# Keybon12_REV_1_0.net
KiCad netlist of a schematic drawn in EAGLE
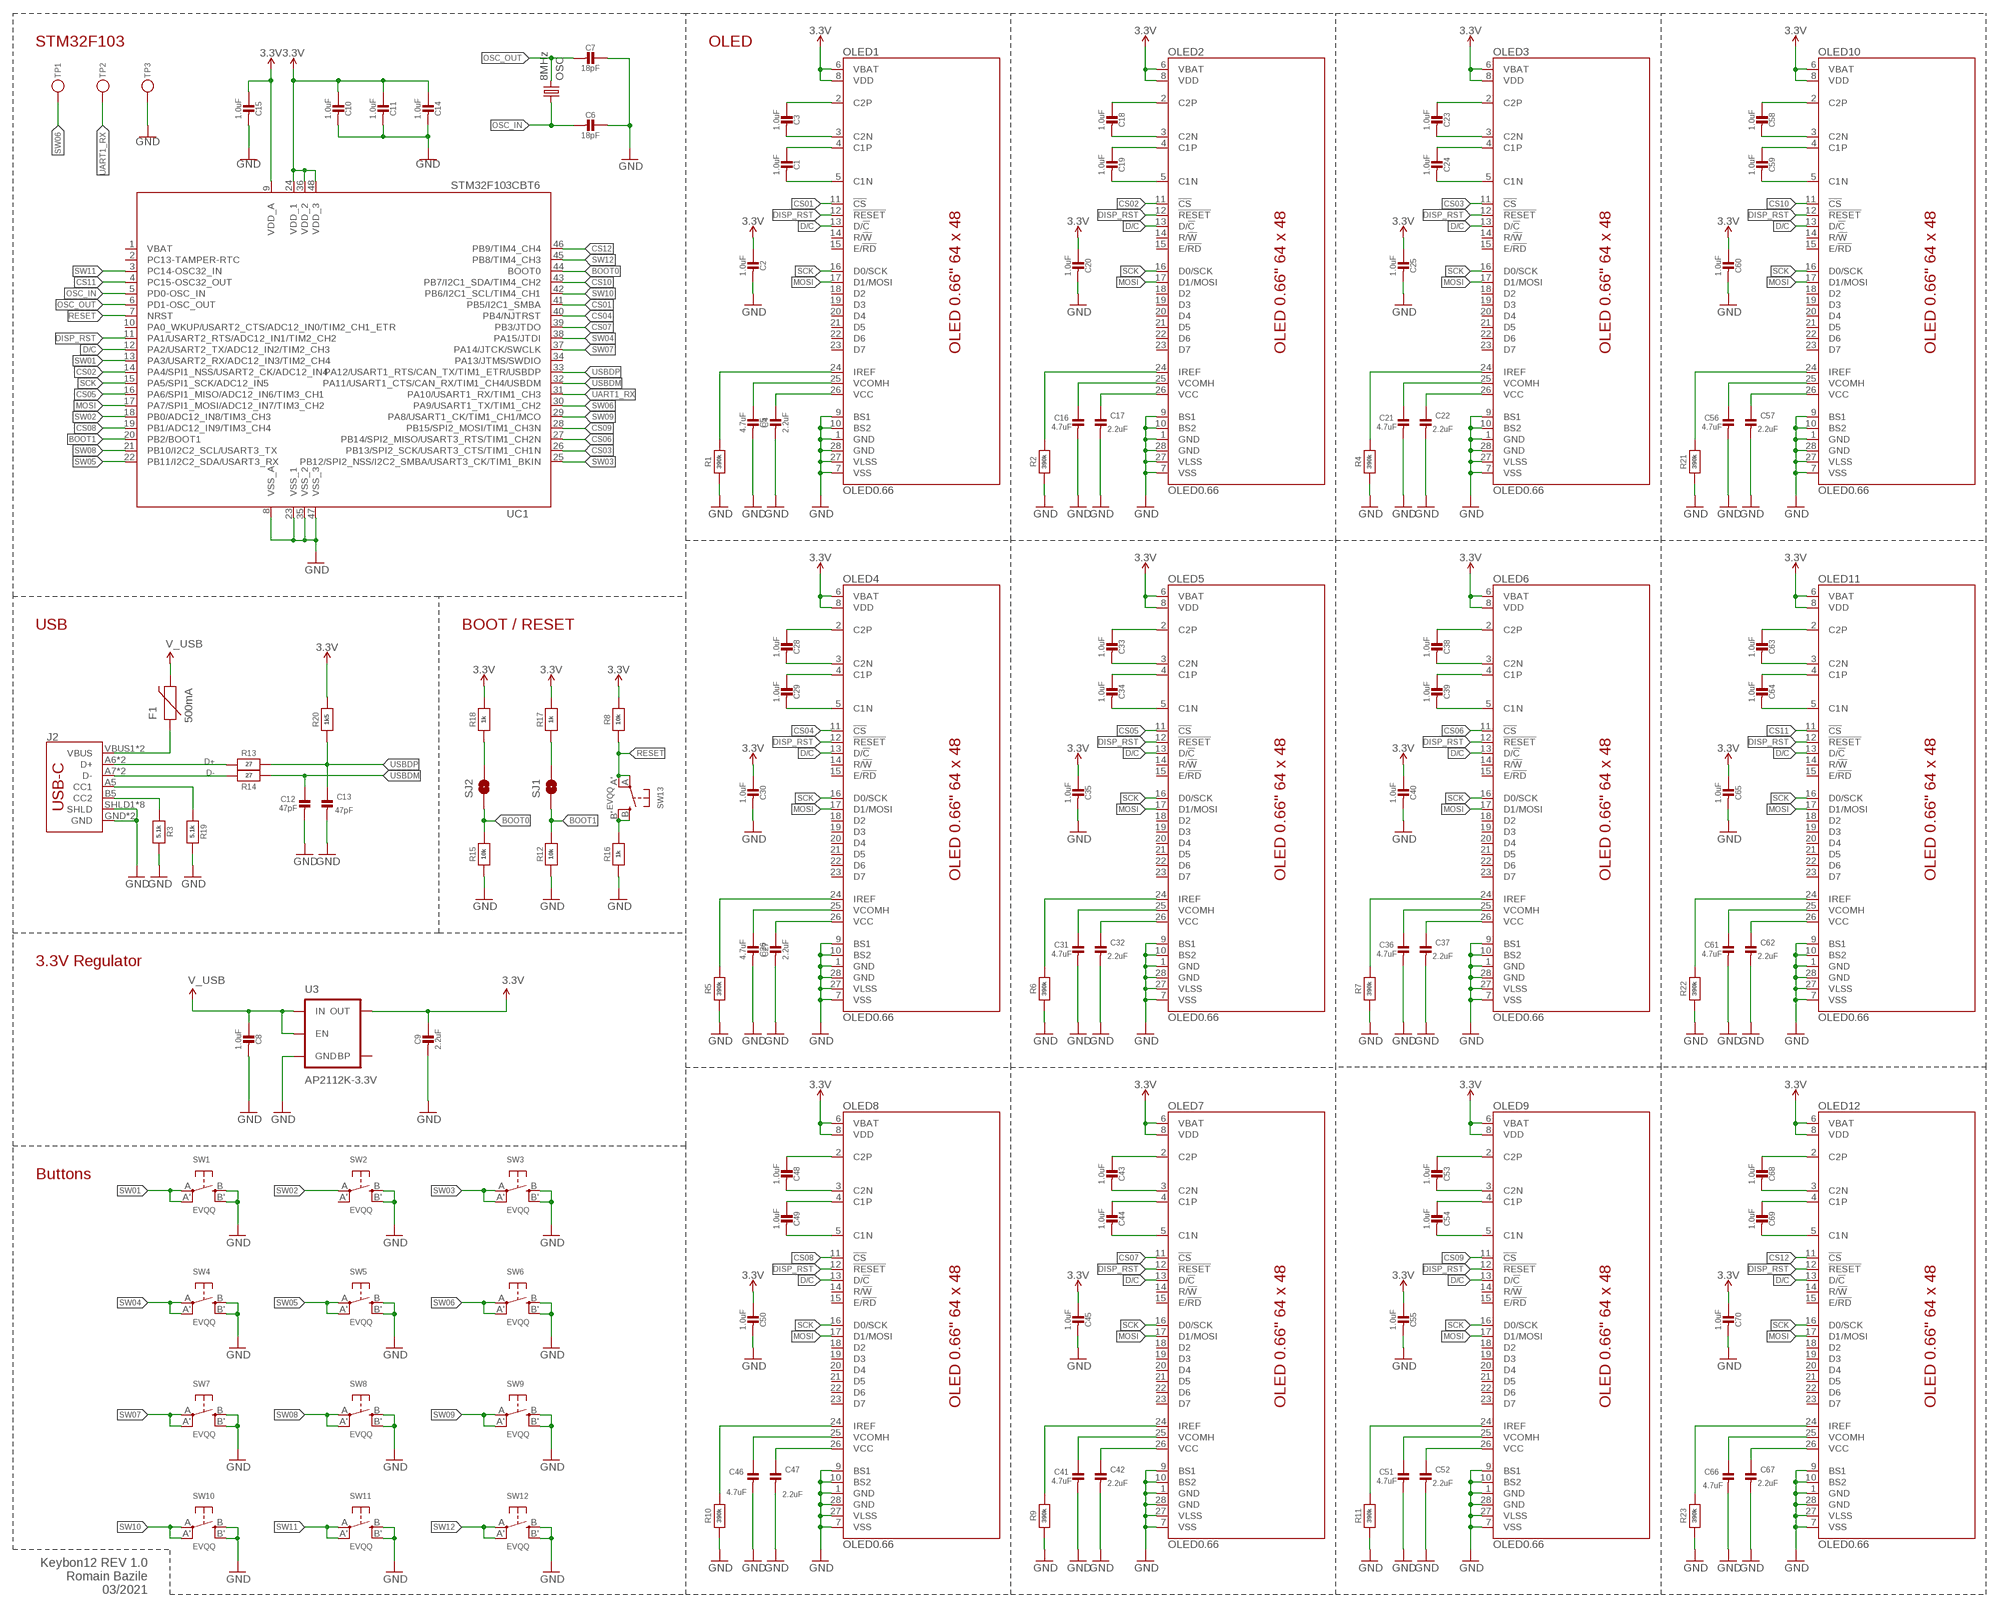
[diagram p0: schematic, sheet 1]

(export (version "E")
  (design (tool "Eeschema 10.0.6"))
  (components
    (comp (ref "C1")
      (value "1.0uF")
      (footprint "eagle-import:_0805MP")
      (libsource (lib "eagle-import") (part "CAP_CERAMIC_0805MP"))
    )
    (comp (ref "C2")
      (value "1.0uF")
      (footprint "eagle-import:_0805MP")
      (libsource (lib "eagle-import") (part "CAP_CERAMIC_0805MP"))
    )
    (comp (ref "C3")
      (value "1.0uF")
      (footprint "eagle-import:_0805MP")
      (libsource (lib "eagle-import") (part "CAP_CERAMIC_0805MP"))
    )
    (comp (ref "C4")
      (value "2.2uF")
      (footprint "eagle-import:_0805MP")
      (libsource (lib "eagle-import") (part "CAP_CERAMIC_0805MP"))
    )
    (comp (ref "C5")
      (value "4.7uF")
      (footprint "eagle-import:_0805MP")
      (libsource (lib "eagle-import") (part "CAP_CERAMIC_0805MP"))
    )
    (comp (ref "C6")
      (value "18pF")
      (footprint "eagle-import:_0805MP")
      (libsource (lib "eagle-import") (part "CAP_CERAMIC_0805MP"))
    )
    (comp (ref "C7")
      (value "18pF")
      (footprint "eagle-import:_0805MP")
      (libsource (lib "eagle-import") (part "CAP_CERAMIC_0805MP"))
    )
    (comp (ref "C8")
      (value "1.0uF")
      (footprint "eagle-import:_0805MP")
      (libsource (lib "eagle-import") (part "CAP_CERAMIC_0805MP"))
    )
    (comp (ref "C9")
      (value "2.2uF")
      (footprint "eagle-import:_0805MP")
      (libsource (lib "eagle-import") (part "CAP_CERAMIC_0805MP"))
    )
    (comp (ref "C10")
      (value "1.0uF")
      (footprint "eagle-import:_0805MP")
      (libsource (lib "eagle-import") (part "CAP_CERAMIC_0805MP"))
    )
    (comp (ref "C11")
      (value "1.0uF")
      (footprint "eagle-import:_0805MP")
      (libsource (lib "eagle-import") (part "CAP_CERAMIC_0805MP"))
    )
    (comp (ref "C12")
      (value "47pF")
      (footprint "eagle-import:_0805MP")
      (libsource (lib "eagle-import") (part "CAP_CERAMIC_0805MP"))
    )
    (comp (ref "C13")
      (value "47pF")
      (footprint "eagle-import:_0805MP")
      (libsource (lib "eagle-import") (part "CAP_CERAMIC_0805MP"))
    )
    (comp (ref "C14")
      (value "1.0uF")
      (footprint "eagle-import:_0805MP")
      (libsource (lib "eagle-import") (part "CAP_CERAMIC_0805MP"))
    )
    (comp (ref "C15")
      (value "1.0uF")
      (footprint "eagle-import:_0805MP")
      (libsource (lib "eagle-import") (part "CAP_CERAMIC_0805MP"))
    )
    (comp (ref "C16")
      (value "4.7uF")
      (footprint "eagle-import:_0805MP")
      (libsource (lib "eagle-import") (part "CAP_CERAMIC_0805MP"))
    )
    (comp (ref "C17")
      (value "2.2uF")
      (footprint "eagle-import:_0805MP")
      (libsource (lib "eagle-import") (part "CAP_CERAMIC_0805MP"))
    )
    (comp (ref "C18")
      (value "1.0uF")
      (footprint "eagle-import:_0805MP")
      (libsource (lib "eagle-import") (part "CAP_CERAMIC_0805MP"))
    )
    (comp (ref "C19")
      (value "1.0uF")
      (footprint "eagle-import:_0805MP")
      (libsource (lib "eagle-import") (part "CAP_CERAMIC_0805MP"))
    )
    (comp (ref "C20")
      (value "1.0uF")
      (footprint "eagle-import:_0805MP")
      (libsource (lib "eagle-import") (part "CAP_CERAMIC_0805MP"))
    )
    (comp (ref "C21")
      (value "4.7uF")
      (footprint "eagle-import:_0805MP")
      (libsource (lib "eagle-import") (part "CAP_CERAMIC_0805MP"))
    )
    (comp (ref "C22")
      (value "2.2uF")
      (footprint "eagle-import:_0805MP")
      (libsource (lib "eagle-import") (part "CAP_CERAMIC_0805MP"))
    )
    (comp (ref "C23")
      (value "1.0uF")
      (footprint "eagle-import:_0805MP")
      (libsource (lib "eagle-import") (part "CAP_CERAMIC_0805MP"))
    )
    (comp (ref "C24")
      (value "1.0uF")
      (footprint "eagle-import:_0805MP")
      (libsource (lib "eagle-import") (part "CAP_CERAMIC_0805MP"))
    )
    (comp (ref "C25")
      (value "1.0uF")
      (footprint "eagle-import:_0805MP")
      (libsource (lib "eagle-import") (part "CAP_CERAMIC_0805MP"))
    )
    (comp (ref "C26")
      (value "4.7uF")
      (footprint "eagle-import:_0805MP")
      (libsource (lib "eagle-import") (part "CAP_CERAMIC_0805MP"))
    )
    (comp (ref "C27")
      (value "2.2uF")
      (footprint "eagle-import:_0805MP")
      (libsource (lib "eagle-import") (part "CAP_CERAMIC_0805MP"))
    )
    (comp (ref "C28")
      (value "1.0uF")
      (footprint "eagle-import:_0805MP")
      (libsource (lib "eagle-import") (part "CAP_CERAMIC_0805MP"))
    )
    (comp (ref "C29")
      (value "1.0uF")
      (footprint "eagle-import:_0805MP")
      (libsource (lib "eagle-import") (part "CAP_CERAMIC_0805MP"))
    )
    (comp (ref "C30")
      (value "1.0uF")
      (footprint "eagle-import:_0805MP")
      (libsource (lib "eagle-import") (part "CAP_CERAMIC_0805MP"))
    )
    (comp (ref "C31")
      (value "4.7uF")
      (footprint "eagle-import:_0805MP")
      (libsource (lib "eagle-import") (part "CAP_CERAMIC_0805MP"))
    )
    (comp (ref "C32")
      (value "2.2uF")
      (footprint "eagle-import:_0805MP")
      (libsource (lib "eagle-import") (part "CAP_CERAMIC_0805MP"))
    )
    (comp (ref "C33")
      (value "1.0uF")
      (footprint "eagle-import:_0805MP")
      (libsource (lib "eagle-import") (part "CAP_CERAMIC_0805MP"))
    )
    (comp (ref "C34")
      (value "1.0uF")
      (footprint "eagle-import:_0805MP")
      (libsource (lib "eagle-import") (part "CAP_CERAMIC_0805MP"))
    )
    (comp (ref "C35")
      (value "1.0uF")
      (footprint "eagle-import:_0805MP")
      (libsource (lib "eagle-import") (part "CAP_CERAMIC_0805MP"))
    )
    (comp (ref "C36")
      (value "4.7uF")
      (footprint "eagle-import:_0805MP")
      (libsource (lib "eagle-import") (part "CAP_CERAMIC_0805MP"))
    )
    (comp (ref "C37")
      (value "2.2uF")
      (footprint "eagle-import:_0805MP")
      (libsource (lib "eagle-import") (part "CAP_CERAMIC_0805MP"))
    )
    (comp (ref "C38")
      (value "1.0uF")
      (footprint "eagle-import:_0805MP")
      (libsource (lib "eagle-import") (part "CAP_CERAMIC_0805MP"))
    )
    (comp (ref "C39")
      (value "1.0uF")
      (footprint "eagle-import:_0805MP")
      (libsource (lib "eagle-import") (part "CAP_CERAMIC_0805MP"))
    )
    (comp (ref "C40")
      (value "1.0uF")
      (footprint "eagle-import:_0805MP")
      (libsource (lib "eagle-import") (part "CAP_CERAMIC_0805MP"))
    )
    (comp (ref "C41")
      (value "4.7uF")
      (footprint "eagle-import:_0805MP")
      (libsource (lib "eagle-import") (part "CAP_CERAMIC_0805MP"))
    )
    (comp (ref "C42")
      (value "2.2uF")
      (footprint "eagle-import:_0805MP")
      (libsource (lib "eagle-import") (part "CAP_CERAMIC_0805MP"))
    )
    (comp (ref "C43")
      (value "1.0uF")
      (footprint "eagle-import:_0805MP")
      (libsource (lib "eagle-import") (part "CAP_CERAMIC_0805MP"))
    )
    (comp (ref "C44")
      (value "1.0uF")
      (footprint "eagle-import:_0805MP")
      (libsource (lib "eagle-import") (part "CAP_CERAMIC_0805MP"))
    )
    (comp (ref "C45")
      (value "1.0uF")
      (footprint "eagle-import:_0805MP")
      (libsource (lib "eagle-import") (part "CAP_CERAMIC_0805MP"))
    )
    (comp (ref "C46")
      (value "4.7uF")
      (footprint "eagle-import:_0805MP")
      (libsource (lib "eagle-import") (part "CAP_CERAMIC_0805MP"))
    )
    (comp (ref "C47")
      (value "2.2uF")
      (footprint "eagle-import:_0805MP")
      (libsource (lib "eagle-import") (part "CAP_CERAMIC_0805MP"))
    )
    (comp (ref "C48")
      (value "1.0uF")
      (footprint "eagle-import:_0805MP")
      (libsource (lib "eagle-import") (part "CAP_CERAMIC_0805MP"))
    )
    (comp (ref "C49")
      (value "1.0uF")
      (footprint "eagle-import:_0805MP")
      (libsource (lib "eagle-import") (part "CAP_CERAMIC_0805MP"))
    )
    (comp (ref "C50")
      (value "1.0uF")
      (footprint "eagle-import:_0805MP")
      (libsource (lib "eagle-import") (part "CAP_CERAMIC_0805MP"))
    )
    (comp (ref "C51")
      (value "4.7uF")
      (footprint "eagle-import:_0805MP")
      (libsource (lib "eagle-import") (part "CAP_CERAMIC_0805MP"))
    )
    (comp (ref "C52")
      (value "2.2uF")
      (footprint "eagle-import:_0805MP")
      (libsource (lib "eagle-import") (part "CAP_CERAMIC_0805MP"))
    )
    (comp (ref "C53")
      (value "1.0uF")
      (footprint "eagle-import:_0805MP")
      (libsource (lib "eagle-import") (part "CAP_CERAMIC_0805MP"))
    )
    (comp (ref "C54")
      (value "1.0uF")
      (footprint "eagle-import:_0805MP")
      (libsource (lib "eagle-import") (part "CAP_CERAMIC_0805MP"))
    )
    (comp (ref "C55")
      (value "1.0uF")
      (footprint "eagle-import:_0805MP")
      (libsource (lib "eagle-import") (part "CAP_CERAMIC_0805MP"))
    )
    (comp (ref "C56")
      (value "4.7uF")
      (footprint "eagle-import:_0805MP")
      (libsource (lib "eagle-import") (part "CAP_CERAMIC_0805MP"))
    )
    (comp (ref "C57")
      (value "2.2uF")
      (footprint "eagle-import:_0805MP")
      (libsource (lib "eagle-import") (part "CAP_CERAMIC_0805MP"))
    )
    (comp (ref "C58")
      (value "1.0uF")
      (footprint "eagle-import:_0805MP")
      (libsource (lib "eagle-import") (part "CAP_CERAMIC_0805MP"))
    )
    (comp (ref "C59")
      (value "1.0uF")
      (footprint "eagle-import:_0805MP")
      (libsource (lib "eagle-import") (part "CAP_CERAMIC_0805MP"))
    )
    (comp (ref "C60")
      (value "1.0uF")
      (footprint "eagle-import:_0805MP")
      (libsource (lib "eagle-import") (part "CAP_CERAMIC_0805MP"))
    )
    (comp (ref "C61")
      (value "4.7uF")
      (footprint "eagle-import:_0805MP")
      (libsource (lib "eagle-import") (part "CAP_CERAMIC_0805MP"))
    )
    (comp (ref "C62")
      (value "2.2uF")
      (footprint "eagle-import:_0805MP")
      (libsource (lib "eagle-import") (part "CAP_CERAMIC_0805MP"))
    )
    (comp (ref "C63")
      (value "1.0uF")
      (footprint "eagle-import:_0805MP")
      (libsource (lib "eagle-import") (part "CAP_CERAMIC_0805MP"))
    )
    (comp (ref "C64")
      (value "1.0uF")
      (footprint "eagle-import:_0805MP")
      (libsource (lib "eagle-import") (part "CAP_CERAMIC_0805MP"))
    )
    (comp (ref "C65")
      (value "1.0uF")
      (footprint "eagle-import:_0805MP")
      (libsource (lib "eagle-import") (part "CAP_CERAMIC_0805MP"))
    )
    (comp (ref "C66")
      (value "4.7uF")
      (footprint "eagle-import:_0805MP")
      (libsource (lib "eagle-import") (part "CAP_CERAMIC_0805MP"))
    )
    (comp (ref "C67")
      (value "2.2uF")
      (footprint "eagle-import:_0805MP")
      (libsource (lib "eagle-import") (part "CAP_CERAMIC_0805MP"))
    )
    (comp (ref "C68")
      (value "1.0uF")
      (footprint "eagle-import:_0805MP")
      (libsource (lib "eagle-import") (part "CAP_CERAMIC_0805MP"))
    )
    (comp (ref "C69")
      (value "1.0uF")
      (footprint "eagle-import:_0805MP")
      (libsource (lib "eagle-import") (part "CAP_CERAMIC_0805MP"))
    )
    (comp (ref "C70")
      (value "1.0uF")
      (footprint "eagle-import:_0805MP")
      (libsource (lib "eagle-import") (part "CAP_CERAMIC_0805MP"))
    )
    (comp (ref "F1")
      (value "500mA")
      (footprint "eagle-import:PTC-1206")
      (libsource (lib "eagle-import") (part "PTCSMD"))
    )
    (comp (ref "J2")
      (value "USB_C16PIN")
      (footprint "eagle-import:USB-C-16P")
      (libsource (lib "eagle-import") (part "USB_C16PIN"))
    )
    (comp (ref "OLED1")
      (value "OLED0.66")
      (footprint "eagle-import:OLED-0.66-64X48")
      (libsource (lib "eagle-import") (part "OLED0.66"))
    )
    (comp (ref "OLED2")
      (value "OLED0.66")
      (footprint "eagle-import:OLED-0.66-64X48")
      (libsource (lib "eagle-import") (part "OLED0.66"))
    )
    (comp (ref "OLED3")
      (value "OLED0.66")
      (footprint "eagle-import:OLED-0.66-64X48")
      (libsource (lib "eagle-import") (part "OLED0.66"))
    )
    (comp (ref "OLED4")
      (value "OLED0.66")
      (footprint "eagle-import:OLED-0.66-64X48")
      (libsource (lib "eagle-import") (part "OLED0.66"))
    )
    (comp (ref "OLED5")
      (value "OLED0.66")
      (footprint "eagle-import:OLED-0.66-64X48")
      (libsource (lib "eagle-import") (part "OLED0.66"))
    )
    (comp (ref "OLED6")
      (value "OLED0.66")
      (footprint "eagle-import:OLED-0.66-64X48")
      (libsource (lib "eagle-import") (part "OLED0.66"))
    )
    (comp (ref "OLED7")
      (value "OLED0.66")
      (footprint "eagle-import:OLED-0.66-64X48")
      (libsource (lib "eagle-import") (part "OLED0.66"))
    )
    (comp (ref "OLED8")
      (value "OLED0.66")
      (footprint "eagle-import:OLED-0.66-64X48")
      (libsource (lib "eagle-import") (part "OLED0.66"))
    )
    (comp (ref "OLED9")
      (value "OLED0.66")
      (footprint "eagle-import:OLED-0.66-64X48")
      (libsource (lib "eagle-import") (part "OLED0.66"))
    )
    (comp (ref "OLED10")
      (value "OLED0.66")
      (footprint "eagle-import:OLED-0.66-64X48")
      (libsource (lib "eagle-import") (part "OLED0.66"))
    )
    (comp (ref "OLED11")
      (value "OLED0.66")
      (footprint "eagle-import:OLED-0.66-64X48")
      (libsource (lib "eagle-import") (part "OLED0.66"))
    )
    (comp (ref "OLED12")
      (value "OLED0.66")
      (footprint "eagle-import:OLED-0.66-64X48")
      (libsource (lib "eagle-import") (part "OLED0.66"))
    )
    (comp (ref "OSC")
      (value "8MHz")
      (footprint "eagle-import:CRYSTAL-SMD-5X3")
      (libsource (lib "eagle-import") (part "CRYSTAL5X3"))
    )
    (comp (ref "R1")
      (value "390k")
      (footprint "eagle-import:_0805MP")
      (libsource (lib "eagle-import") (part "RESISTOR_0805MP"))
    )
    (comp (ref "R2")
      (value "390k")
      (footprint "eagle-import:_0805MP")
      (libsource (lib "eagle-import") (part "RESISTOR_0805MP"))
    )
    (comp (ref "R3")
      (value "5.1k")
      (footprint "eagle-import:_0805MP")
      (libsource (lib "eagle-import") (part "RESISTOR_0805MP"))
    )
    (comp (ref "R4")
      (value "390k")
      (footprint "eagle-import:_0805MP")
      (libsource (lib "eagle-import") (part "RESISTOR_0805MP"))
    )
    (comp (ref "R5")
      (value "390k")
      (footprint "eagle-import:_0805MP")
      (libsource (lib "eagle-import") (part "RESISTOR_0805MP"))
    )
    (comp (ref "R6")
      (value "390k")
      (footprint "eagle-import:_0805MP")
      (libsource (lib "eagle-import") (part "RESISTOR_0805MP"))
    )
    (comp (ref "R7")
      (value "390k")
      (footprint "eagle-import:_0805MP")
      (libsource (lib "eagle-import") (part "RESISTOR_0805MP"))
    )
    (comp (ref "R8")
      (value "10k")
      (footprint "eagle-import:_0805MP")
      (libsource (lib "eagle-import") (part "RESISTOR_0805MP"))
    )
    (comp (ref "R9")
      (value "390k")
      (footprint "eagle-import:_0805MP")
      (libsource (lib "eagle-import") (part "RESISTOR_0805MP"))
    )
    (comp (ref "R10")
      (value "390k")
      (footprint "eagle-import:_0805MP")
      (libsource (lib "eagle-import") (part "RESISTOR_0805MP"))
    )
    (comp (ref "R11")
      (value "390k")
      (footprint "eagle-import:_0805MP")
      (libsource (lib "eagle-import") (part "RESISTOR_0805MP"))
    )
    (comp (ref "R12")
      (value "10k")
      (footprint "eagle-import:_0805MP")
      (libsource (lib "eagle-import") (part "RESISTOR_0805MP"))
    )
    (comp (ref "R13")
      (value "27")
      (footprint "eagle-import:_0805MP")
      (libsource (lib "eagle-import") (part "RESISTOR_0805MP"))
    )
    (comp (ref "R14")
      (value "27")
      (footprint "eagle-import:_0805MP")
      (libsource (lib "eagle-import") (part "RESISTOR_0805MP"))
    )
    (comp (ref "R15")
      (value "10k")
      (footprint "eagle-import:_0805MP")
      (libsource (lib "eagle-import") (part "RESISTOR_0805MP"))
    )
    (comp (ref "R16")
      (value "1k")
      (footprint "eagle-import:_0805MP")
      (libsource (lib "eagle-import") (part "RESISTOR_0805MP"))
    )
    (comp (ref "R17")
      (value "1k")
      (footprint "eagle-import:_0805MP")
      (libsource (lib "eagle-import") (part "RESISTOR_0805MP"))
    )
    (comp (ref "R18")
      (value "1k")
      (footprint "eagle-import:_0805MP")
      (libsource (lib "eagle-import") (part "RESISTOR_0805MP"))
    )
    (comp (ref "R19")
      (value "5.1k")
      (footprint "eagle-import:_0805MP")
      (libsource (lib "eagle-import") (part "RESISTOR_0805MP"))
    )
    (comp (ref "R20")
      (value "1k5")
      (footprint "eagle-import:_0805MP")
      (libsource (lib "eagle-import") (part "RESISTOR_0805MP"))
    )
    (comp (ref "R21")
      (value "390k")
      (footprint "eagle-import:_0805MP")
      (libsource (lib "eagle-import") (part "RESISTOR_0805MP"))
    )
    (comp (ref "R22")
      (value "390k")
      (footprint "eagle-import:_0805MP")
      (libsource (lib "eagle-import") (part "RESISTOR_0805MP"))
    )
    (comp (ref "R23")
      (value "390k")
      (footprint "eagle-import:_0805MP")
      (libsource (lib "eagle-import") (part "RESISTOR_0805MP"))
    )
    (comp (ref "SJ1")
      (value "JUMPER-PAD-2-NOYES_SILK")
      (footprint "eagle-import:PAD-JUMPER-2-NO_YES_SILK")
      (libsource (lib "eagle-import") (part "JUMPER-PAD-2-NOYES_SILK"))
    )
    (comp (ref "SJ2")
      (value "JUMPER-PAD-2-NOYES_SILK")
      (footprint "eagle-import:PAD-JUMPER-2-NO_YES_SILK")
      (libsource (lib "eagle-import") (part "JUMPER-PAD-2-NOYES_SILK"))
    )
    (comp (ref "SW1")
      (value "EVQQ")
      (footprint "eagle-import:EVQ-Q2_SMALLER")
      (libsource (lib "eagle-import") (part "SWITCH_TACT_SMT_EVQQ2_SMALL"))
    )
    (comp (ref "SW2")
      (value "EVQQ")
      (footprint "eagle-import:EVQ-Q2_SMALLER")
      (libsource (lib "eagle-import") (part "SWITCH_TACT_SMT_EVQQ2_SMALL"))
    )
    (comp (ref "SW3")
      (value "EVQQ")
      (footprint "eagle-import:EVQ-Q2_SMALLER")
      (libsource (lib "eagle-import") (part "SWITCH_TACT_SMT_EVQQ2_SMALL"))
    )
    (comp (ref "SW4")
      (value "EVQQ")
      (footprint "eagle-import:EVQ-Q2_SMALLER")
      (libsource (lib "eagle-import") (part "SWITCH_TACT_SMT_EVQQ2_SMALL"))
    )
    (comp (ref "SW5")
      (value "EVQQ")
      (footprint "eagle-import:EVQ-Q2_SMALLER")
      (libsource (lib "eagle-import") (part "SWITCH_TACT_SMT_EVQQ2_SMALL"))
    )
    (comp (ref "SW6")
      (value "EVQQ")
      (footprint "eagle-import:EVQ-Q2_SMALLER")
      (libsource (lib "eagle-import") (part "SWITCH_TACT_SMT_EVQQ2_SMALL"))
    )
    (comp (ref "SW7")
      (value "EVQQ")
      (footprint "eagle-import:EVQ-Q2_SMALLER")
      (libsource (lib "eagle-import") (part "SWITCH_TACT_SMT_EVQQ2_SMALL"))
    )
    (comp (ref "SW8")
      (value "EVQQ")
      (footprint "eagle-import:EVQ-Q2_SMALLER")
      (libsource (lib "eagle-import") (part "SWITCH_TACT_SMT_EVQQ2_SMALL"))
    )
    (comp (ref "SW9")
      (value "EVQQ")
      (footprint "eagle-import:EVQ-Q2_SMALLER")
      (libsource (lib "eagle-import") (part "SWITCH_TACT_SMT_EVQQ2_SMALL"))
    )
    (comp (ref "SW10")
      (value "EVQQ")
      (footprint "eagle-import:EVQ-Q2_SMALLER")
      (libsource (lib "eagle-import") (part "SWITCH_TACT_SMT_EVQQ2_SMALL"))
    )
    (comp (ref "SW11")
      (value "EVQQ")
      (footprint "eagle-import:EVQ-Q2_SMALLER")
      (libsource (lib "eagle-import") (part "SWITCH_TACT_SMT_EVQQ2_SMALL"))
    )
    (comp (ref "SW12")
      (value "EVQQ")
      (footprint "eagle-import:EVQ-Q2_SMALLER")
      (libsource (lib "eagle-import") (part "SWITCH_TACT_SMT_EVQQ2_SMALL"))
    )
    (comp (ref "SW13")
      (value "EVQQ")
      (footprint "eagle-import:EVQ-Q2_SMALLER")
      (libsource (lib "eagle-import") (part "SWITCH_TACT_SMT_EVQQ2_SMALL"))
    )
    (comp (ref "TP1")
      (value "TESTPOINTPAD2MM")
      (footprint "eagle-import:TESTPOINT_PAD_2MM")
      (libsource (lib "eagle-import") (part "TESTPOINTPAD2MM"))
    )
    (comp (ref "TP2")
      (value "TESTPOINTPAD2MM")
      (footprint "eagle-import:TESTPOINT_PAD_2MM")
      (libsource (lib "eagle-import") (part "TESTPOINTPAD2MM"))
    )
    (comp (ref "TP3")
      (value "TESTPOINTPAD2MM")
      (footprint "eagle-import:TESTPOINT_PAD_2MM")
      (libsource (lib "eagle-import") (part "TESTPOINTPAD2MM"))
    )
    (comp (ref "U3")
      (value "AP2112K-3.3V")
      (footprint "eagle-import:SOT23-5")
      (libsource (lib "eagle-import") (part "V_REG_LDOSMD"))
    )
    (comp (ref "UC1")
      (value "STM32F103CBT6")
      (footprint "eagle-import:LQFP48")
      (libsource (lib "eagle-import") (part "STM32F103CB"))
    )
  )
  (nets
    (net (code "1") (name "/D+") (class "Default")
      (node (ref "J2") (pin "A6") (pinfunction "D+_A6") (pintype "bidirectional"))
      (node (ref "J2") (pin "B6") (pinfunction "D+_B6") (pintype "bidirectional"))
      (node (ref "R13") (pin "1") (pinfunction "1_1") (pintype "passive"))
    )
    (net (code "2") (name "/D-") (class "Default")
      (node (ref "J2") (pin "A7") (pinfunction "D-_A7") (pintype "bidirectional"))
      (node (ref "J2") (pin "B7") (pinfunction "D-_B7") (pintype "bidirectional"))
      (node (ref "R14") (pin "1") (pinfunction "1_1") (pintype "passive"))
    )
    (net (code "3") (name "/VBAT") (class "Default")
      (node (ref "UC1") (pin "1") (pinfunction "VBAT_1") (pintype "power_in"))
    )
    (net (code "4") (name "3.3V") (class "Default")
      (node (ref "C10") (pin "1") (pinfunction "1_1") (pintype "passive"))
      (node (ref "C11") (pin "1") (pinfunction "1_1") (pintype "passive"))
      (node (ref "C14") (pin "1") (pinfunction "1_1") (pintype "passive"))
      (node (ref "C15") (pin "1") (pinfunction "1_1") (pintype "passive"))
      (node (ref "C2") (pin "1") (pinfunction "1_1") (pintype "passive"))
      (node (ref "C20") (pin "1") (pinfunction "1_1") (pintype "passive"))
      (node (ref "C25") (pin "1") (pinfunction "1_1") (pintype "passive"))
      (node (ref "C30") (pin "1") (pinfunction "1_1") (pintype "passive"))
      (node (ref "C35") (pin "1") (pinfunction "1_1") (pintype "passive"))
      (node (ref "C40") (pin "1") (pinfunction "1_1") (pintype "passive"))
      (node (ref "C45") (pin "1") (pinfunction "1_1") (pintype "passive"))
      (node (ref "C50") (pin "1") (pinfunction "1_1") (pintype "passive"))
      (node (ref "C55") (pin "1") (pinfunction "1_1") (pintype "passive"))
      (node (ref "C60") (pin "1") (pinfunction "1_1") (pintype "passive"))
      (node (ref "C65") (pin "1") (pinfunction "1_1") (pintype "passive"))
      (node (ref "C70") (pin "1") (pinfunction "1_1") (pintype "passive"))
      (node (ref "C9") (pin "1") (pinfunction "1_1") (pintype "passive"))
      (node (ref "OLED1") (pin "6") (pinfunction "VBAT_6") (pintype "bidirectional"))
      (node (ref "OLED1") (pin "8") (pinfunction "VDD_8") (pintype "bidirectional"))
      (node (ref "OLED10") (pin "6") (pinfunction "VBAT_6") (pintype "bidirectional"))
      (node (ref "OLED10") (pin "8") (pinfunction "VDD_8") (pintype "bidirectional"))
      (node (ref "OLED11") (pin "6") (pinfunction "VBAT_6") (pintype "bidirectional"))
      (node (ref "OLED11") (pin "8") (pinfunction "VDD_8") (pintype "bidirectional"))
      (node (ref "OLED12") (pin "6") (pinfunction "VBAT_6") (pintype "bidirectional"))
      (node (ref "OLED12") (pin "8") (pinfunction "VDD_8") (pintype "bidirectional"))
      (node (ref "OLED2") (pin "6") (pinfunction "VBAT_6") (pintype "bidirectional"))
      (node (ref "OLED2") (pin "8") (pinfunction "VDD_8") (pintype "bidirectional"))
      (node (ref "OLED3") (pin "6") (pinfunction "VBAT_6") (pintype "bidirectional"))
      (node (ref "OLED3") (pin "8") (pinfunction "VDD_8") (pintype "bidirectional"))
      (node (ref "OLED4") (pin "6") (pinfunction "VBAT_6") (pintype "bidirectional"))
      (node (ref "OLED4") (pin "8") (pinfunction "VDD_8") (pintype "bidirectional"))
      (node (ref "OLED5") (pin "6") (pinfunction "VBAT_6") (pintype "bidirectional"))
      (node (ref "OLED5") (pin "8") (pinfunction "VDD_8") (pintype "bidirectional"))
      (node (ref "OLED6") (pin "6") (pinfunction "VBAT_6") (pintype "bidirectional"))
      (node (ref "OLED6") (pin "8") (pinfunction "VDD_8") (pintype "bidirectional"))
      (node (ref "OLED7") (pin "6") (pinfunction "VBAT_6") (pintype "bidirectional"))
      (node (ref "OLED7") (pin "8") (pinfunction "VDD_8") (pintype "bidirectional"))
      (node (ref "OLED8") (pin "6") (pinfunction "VBAT_6") (pintype "bidirectional"))
      (node (ref "OLED8") (pin "8") (pinfunction "VDD_8") (pintype "bidirectional"))
      (node (ref "OLED9") (pin "6") (pinfunction "VBAT_6") (pintype "bidirectional"))
      (node (ref "OLED9") (pin "8") (pinfunction "VDD_8") (pintype "bidirectional"))
      (node (ref "R17") (pin "2") (pinfunction "2_2") (pintype "passive"))
      (node (ref "R18") (pin "2") (pinfunction "2_2") (pintype "passive"))
      (node (ref "R20") (pin "2") (pinfunction "2_2") (pintype "passive"))
      (node (ref "R8") (pin "2") (pinfunction "2_2") (pintype "passive"))
      (node (ref "U3") (pin "5") (pinfunction "OUT_5") (pintype "passive"))
      (node (ref "UC1") (pin "24") (pinfunction "VDD_1_24") (pintype "power_in"))
      (node (ref "UC1") (pin "36") (pinfunction "VDD_2_36") (pintype "power_in"))
      (node (ref "UC1") (pin "48") (pinfunction "VDD_3_48") (pintype "power_in"))
      (node (ref "UC1") (pin "9") (pinfunction "VDD_A_9") (pintype "power_in"))
    )
    (net (code "5") (name "BOOT0") (class "Default")
      (node (ref "R15") (pin "2") (pinfunction "2_2") (pintype "passive"))
      (node (ref "SJ2") (pin "1") (pinfunction "1_1") (pintype "passive"))
      (node (ref "UC1") (pin "44") (pinfunction "BOOT0_44") (pintype "input"))
    )
    (net (code "6") (name "BOOT1") (class "Default")
      (node (ref "R12") (pin "2") (pinfunction "2_2") (pintype "passive"))
      (node (ref "SJ1") (pin "1") (pinfunction "1_1") (pintype "passive"))
      (node (ref "UC1") (pin "20") (pinfunction "PB2/BOOT1_20") (pintype "bidirectional"))
    )
    (net (code "7") (name "CS01") (class "Default")
      (node (ref "OLED1") (pin "11") (pinfunction "~{CS}_11") (pintype "bidirectional"))
      (node (ref "UC1") (pin "41") (pinfunction "PB5/I2C1_SMBA_41") (pintype "input"))
    )
    (net (code "8") (name "CS02") (class "Default")
      (node (ref "OLED2") (pin "11") (pinfunction "~{CS}_11") (pintype "bidirectional"))
      (node (ref "UC1") (pin "14") (pinfunction "PA4/SPI1_NSS/USART2_CK/ADC12_IN4_14") (pintype "bidirectional"))
    )
    (net (code "9") (name "CS03") (class "Default")
      (node (ref "OLED3") (pin "11") (pinfunction "~{CS}_11") (pintype "bidirectional"))
      (node (ref "UC1") (pin "26") (pinfunction "PB13/SPI2_SCK/USART3_CTS/TIM1_CH1N_26") (pintype "input"))
    )
    (net (code "10") (name "CS04") (class "Default")
      (node (ref "OLED4") (pin "11") (pinfunction "~{CS}_11") (pintype "bidirectional"))
      (node (ref "UC1") (pin "40") (pinfunction "PB4/NJTRST_40") (pintype "bidirectional"))
    )
    (net (code "11") (name "CS05") (class "Default")
      (node (ref "OLED5") (pin "11") (pinfunction "~{CS}_11") (pintype "bidirectional"))
      (node (ref "UC1") (pin "16") (pinfunction "PA6/SPI1_MISO/ADC12_IN6/TIM3_CH1_16") (pintype "bidirectional"))
    )
    (net (code "12") (name "CS06") (class "Default")
      (node (ref "OLED6") (pin "11") (pinfunction "~{CS}_11") (pintype "bidirectional"))
      (node (ref "UC1") (pin "27") (pinfunction "PB14/SPI2_MISO/USART3_RTS/TIM1_CH2N_27") (pintype "input"))
    )
    (net (code "13") (name "CS07") (class "Default")
      (node (ref "OLED7") (pin "11") (pinfunction "~{CS}_11") (pintype "bidirectional"))
      (node (ref "UC1") (pin "39") (pinfunction "PB3/JTDO_39") (pintype "bidirectional"))
    )
    (net (code "14") (name "CS08") (class "Default")
      (node (ref "OLED8") (pin "11") (pinfunction "~{CS}_11") (pintype "bidirectional"))
      (node (ref "UC1") (pin "19") (pinfunction "PB1/ADC12_IN9/TIM3_CH4_19") (pintype "bidirectional"))
    )
    (net (code "15") (name "CS09") (class "Default")
      (node (ref "OLED9") (pin "11") (pinfunction "~{CS}_11") (pintype "bidirectional"))
      (node (ref "UC1") (pin "28") (pinfunction "PB15/SPI2_MOSI/TIM1_CH3N_28") (pintype "input"))
    )
    (net (code "16") (name "CS10") (class "Default")
      (node (ref "OLED10") (pin "11") (pinfunction "~{CS}_11") (pintype "bidirectional"))
      (node (ref "UC1") (pin "43") (pinfunction "PB7/I2C1_SDA/TIM4_CH2_43") (pintype "bidirectional"))
    )
    (net (code "17") (name "CS11") (class "Default")
      (node (ref "OLED11") (pin "11") (pinfunction "~{CS}_11") (pintype "bidirectional"))
      (node (ref "UC1") (pin "4") (pinfunction "PC15-OSC32_OUT_4") (pintype "input"))
    )
    (net (code "18") (name "CS12") (class "Default")
      (node (ref "OLED12") (pin "11") (pinfunction "~{CS}_11") (pintype "bidirectional"))
      (node (ref "UC1") (pin "46") (pinfunction "PB9/TIM4_CH4_46") (pintype "input"))
    )
    (net (code "19") (name "DISP_RST") (class "Default")
      (node (ref "OLED1") (pin "12") (pinfunction "~{RESET}_12") (pintype "bidirectional"))
      (node (ref "OLED10") (pin "12") (pinfunction "~{RESET}_12") (pintype "bidirectional"))
      (node (ref "OLED11") (pin "12") (pinfunction "~{RESET}_12") (pintype "bidirectional"))
      (node (ref "OLED12") (pin "12") (pinfunction "~{RESET}_12") (pintype "bidirectional"))
      (node (ref "OLED2") (pin "12") (pinfunction "~{RESET}_12") (pintype "bidirectional"))
      (node (ref "OLED3") (pin "12") (pinfunction "~{RESET}_12") (pintype "bidirectional"))
      (node (ref "OLED4") (pin "12") (pinfunction "~{RESET}_12") (pintype "bidirectional"))
      (node (ref "OLED5") (pin "12") (pinfunction "~{RESET}_12") (pintype "bidirectional"))
      (node (ref "OLED6") (pin "12") (pinfunction "~{RESET}_12") (pintype "bidirectional"))
      (node (ref "OLED7") (pin "12") (pinfunction "~{RESET}_12") (pintype "bidirectional"))
      (node (ref "OLED8") (pin "12") (pinfunction "~{RESET}_12") (pintype "bidirectional"))
      (node (ref "OLED9") (pin "12") (pinfunction "~{RESET}_12") (pintype "bidirectional"))
      (node (ref "UC1") (pin "11") (pinfunction "PA1/USART2_RTS/ADC12_IN1/TIM2_CH2_11") (pintype "bidirectional"))
    )
    (net (code "20") (name "D{slash}C") (class "Default")
      (node (ref "OLED1") (pin "13") (pinfunction "D/~{C}_13") (pintype "bidirectional"))
      (node (ref "OLED10") (pin "13") (pinfunction "D/~{C}_13") (pintype "bidirectional"))
      (node (ref "OLED11") (pin "13") (pinfunction "D/~{C}_13") (pintype "bidirectional"))
      (node (ref "OLED12") (pin "13") (pinfunction "D/~{C}_13") (pintype "bidirectional"))
      (node (ref "OLED2") (pin "13") (pinfunction "D/~{C}_13") (pintype "bidirectional"))
      (node (ref "OLED3") (pin "13") (pinfunction "D/~{C}_13") (pintype "bidirectional"))
      (node (ref "OLED4") (pin "13") (pinfunction "D/~{C}_13") (pintype "bidirectional"))
      (node (ref "OLED5") (pin "13") (pinfunction "D/~{C}_13") (pintype "bidirectional"))
      (node (ref "OLED6") (pin "13") (pinfunction "D/~{C}_13") (pintype "bidirectional"))
      (node (ref "OLED7") (pin "13") (pinfunction "D/~{C}_13") (pintype "bidirectional"))
      (node (ref "OLED8") (pin "13") (pinfunction "D/~{C}_13") (pintype "bidirectional"))
      (node (ref "OLED9") (pin "13") (pinfunction "D/~{C}_13") (pintype "bidirectional"))
      (node (ref "UC1") (pin "12") (pinfunction "PA2/USART2_TX/ADC12_IN2/TIM2_CH3_12") (pintype "bidirectional"))
    )
    (net (code "21") (name "GND") (class "Default")
      (node (ref "C10") (pin "2") (pinfunction "2_2") (pintype "passive"))
      (node (ref "C11") (pin "2") (pinfunction "2_2") (pintype "passive"))
      (node (ref "C12") (pin "2") (pinfunction "2_2") (pintype "passive"))
      (node (ref "C13") (pin "2") (pinfunction "2_2") (pintype "passive"))
      (node (ref "C14") (pin "2") (pinfunction "2_2") (pintype "passive"))
      (node (ref "C15") (pin "2") (pinfunction "2_2") (pintype "passive"))
      (node (ref "C16") (pin "2") (pinfunction "2_2") (pintype "passive"))
      (node (ref "C17") (pin "2") (pinfunction "2_2") (pintype "passive"))
      (node (ref "C2") (pin "2") (pinfunction "2_2") (pintype "passive"))
      (node (ref "C20") (pin "2") (pinfunction "2_2") (pintype "passive"))
      (node (ref "C21") (pin "2") (pinfunction "2_2") (pintype "passive"))
      (node (ref "C22") (pin "2") (pinfunction "2_2") (pintype "passive"))
      (node (ref "C25") (pin "2") (pinfunction "2_2") (pintype "passive"))
      (node (ref "C26") (pin "2") (pinfunction "2_2") (pintype "passive"))
      (node (ref "C27") (pin "2") (pinfunction "2_2") (pintype "passive"))
      (node (ref "C30") (pin "2") (pinfunction "2_2") (pintype "passive"))
      (node (ref "C31") (pin "2") (pinfunction "2_2") (pintype "passive"))
      (node (ref "C32") (pin "2") (pinfunction "2_2") (pintype "passive"))
      (node (ref "C35") (pin "2") (pinfunction "2_2") (pintype "passive"))
      (node (ref "C36") (pin "2") (pinfunction "2_2") (pintype "passive"))
      (node (ref "C37") (pin "2") (pinfunction "2_2") (pintype "passive"))
      (node (ref "C4") (pin "2") (pinfunction "2_2") (pintype "passive"))
      (node (ref "C40") (pin "2") (pinfunction "2_2") (pintype "passive"))
      (node (ref "C41") (pin "2") (pinfunction "2_2") (pintype "passive"))
      (node (ref "C42") (pin "2") (pinfunction "2_2") (pintype "passive"))
      (node (ref "C45") (pin "2") (pinfunction "2_2") (pintype "passive"))
      (node (ref "C46") (pin "2") (pinfunction "2_2") (pintype "passive"))
      (node (ref "C47") (pin "2") (pinfunction "2_2") (pintype "passive"))
      (node (ref "C5") (pin "2") (pinfunction "2_2") (pintype "passive"))
      (node (ref "C50") (pin "2") (pinfunction "2_2") (pintype "passive"))
      (node (ref "C51") (pin "2") (pinfunction "2_2") (pintype "passive"))
      (node (ref "C52") (pin "2") (pinfunction "2_2") (pintype "passive"))
      (node (ref "C55") (pin "2") (pinfunction "2_2") (pintype "passive"))
      (node (ref "C56") (pin "2") (pinfunction "2_2") (pintype "passive"))
      (node (ref "C57") (pin "2") (pinfunction "2_2") (pintype "passive"))
      (node (ref "C6") (pin "1") (pinfunction "1_1") (pintype "passive"))
      (node (ref "C60") (pin "2") (pinfunction "2_2") (pintype "passive"))
      (node (ref "C61") (pin "2") (pinfunction "2_2") (pintype "passive"))
      (node (ref "C62") (pin "2") (pinfunction "2_2") (pintype "passive"))
      (node (ref "C65") (pin "2") (pinfunction "2_2") (pintype "passive"))
      (node (ref "C66") (pin "2") (pinfunction "2_2") (pintype "passive"))
      (node (ref "C67") (pin "2") (pinfunction "2_2") (pintype "passive"))
      (node (ref "C7") (pin "1") (pinfunction "1_1") (pintype "passive"))
      (node (ref "C70") (pin "2") (pinfunction "2_2") (pintype "passive"))
      (node (ref "C8") (pin "2") (pinfunction "2_2") (pintype "passive"))
      (node (ref "C9") (pin "2") (pinfunction "2_2") (pintype "passive"))
      (node (ref "J2") (pin "GND") (pinfunction "GND_GND") (pintype "bidirectional"))
      (node (ref "J2") (pin "GND2") (pinfunction "GND_GND2") (pintype "bidirectional"))
      (node (ref "J2") (pin "SHLD1") (pinfunction "SHLD_SHLD1") (pintype "bidirectional"))
      (node (ref "J2") (pin "SHLD2") (pinfunction "SHLD_SHLD2") (pintype "bidirectional"))
      (node (ref "J2") (pin "SHLD3") (pinfunction "SHLD_SHLD3") (pintype "bidirectional"))
      (node (ref "J2") (pin "SHLD4") (pinfunction "SHLD_SHLD4") (pintype "bidirectional"))
      (node (ref "J2") (pin "SHLD5") (pinfunction "SHLD_SHLD5") (pintype "bidirectional"))
      (node (ref "J2") (pin "SHLD6") (pinfunction "SHLD_SHLD6") (pintype "bidirectional"))
      (node (ref "J2") (pin "SHLD7") (pinfunction "SHLD_SHLD7") (pintype "bidirectional"))
      (node (ref "J2") (pin "SHLD8") (pinfunction "SHLD_SHLD8") (pintype "bidirectional"))
      (node (ref "OLED1") (pin "1") (pinfunction "GND_1") (pintype "bidirectional"))
      (node (ref "OLED1") (pin "10") (pinfunction "BS2_10") (pintype "bidirectional"))
      (node (ref "OLED1") (pin "27") (pinfunction "VLSS_27") (pintype "bidirectional"))
      (node (ref "OLED1") (pin "28") (pinfunction "GND_28") (pintype "bidirectional"))
      (node (ref "OLED1") (pin "7") (pinfunction "VSS_7") (pintype "bidirectional"))
      (node (ref "OLED1") (pin "9") (pinfunction "BS1_9") (pintype "bidirectional"))
      (node (ref "OLED10") (pin "1") (pinfunction "GND_1") (pintype "bidirectional"))
      (node (ref "OLED10") (pin "10") (pinfunction "BS2_10") (pintype "bidirectional"))
      (node (ref "OLED10") (pin "27") (pinfunction "VLSS_27") (pintype "bidirectional"))
      (node (ref "OLED10") (pin "28") (pinfunction "GND_28") (pintype "bidirectional"))
      (node (ref "OLED10") (pin "7") (pinfunction "VSS_7") (pintype "bidirectional"))
      (node (ref "OLED10") (pin "9") (pinfunction "BS1_9") (pintype "bidirectional"))
      (node (ref "OLED11") (pin "1") (pinfunction "GND_1") (pintype "bidirectional"))
      (node (ref "OLED11") (pin "10") (pinfunction "BS2_10") (pintype "bidirectional"))
      (node (ref "OLED11") (pin "27") (pinfunction "VLSS_27") (pintype "bidirectional"))
      (node (ref "OLED11") (pin "28") (pinfunction "GND_28") (pintype "bidirectional"))
      (node (ref "OLED11") (pin "7") (pinfunction "VSS_7") (pintype "bidirectional"))
      (node (ref "OLED11") (pin "9") (pinfunction "BS1_9") (pintype "bidirectional"))
      (node (ref "OLED12") (pin "1") (pinfunction "GND_1") (pintype "bidirectional"))
      (node (ref "OLED12") (pin "10") (pinfunction "BS2_10") (pintype "bidirectional"))
      (node (ref "OLED12") (pin "27") (pinfunction "VLSS_27") (pintype "bidirectional"))
      (node (ref "OLED12") (pin "28") (pinfunction "GND_28") (pintype "bidirectional"))
      (node (ref "OLED12") (pin "7") (pinfunction "VSS_7") (pintype "bidirectional"))
      (node (ref "OLED12") (pin "9") (pinfunction "BS1_9") (pintype "bidirectional"))
      (node (ref "OLED2") (pin "1") (pinfunction "GND_1") (pintype "bidirectional"))
      (node (ref "OLED2") (pin "10") (pinfunction "BS2_10") (pintype "bidirectional"))
      (node (ref "OLED2") (pin "27") (pinfunction "VLSS_27") (pintype "bidirectional"))
      (node (ref "OLED2") (pin "28") (pinfunction "GND_28") (pintype "bidirectional"))
      (node (ref "OLED2") (pin "7") (pinfunction "VSS_7") (pintype "bidirectional"))
      (node (ref "OLED2") (pin "9") (pinfunction "BS1_9") (pintype "bidirectional"))
      (node (ref "OLED3") (pin "1") (pinfunction "GND_1") (pintype "bidirectional"))
      (node (ref "OLED3") (pin "10") (pinfunction "BS2_10") (pintype "bidirectional"))
      (node (ref "OLED3") (pin "27") (pinfunction "VLSS_27") (pintype "bidirectional"))
      (node (ref "OLED3") (pin "28") (pinfunction "GND_28") (pintype "bidirectional"))
      (node (ref "OLED3") (pin "7") (pinfunction "VSS_7") (pintype "bidirectional"))
      (node (ref "OLED3") (pin "9") (pinfunction "BS1_9") (pintype "bidirectional"))
      (node (ref "OLED4") (pin "1") (pinfunction "GND_1") (pintype "bidirectional"))
      (node (ref "OLED4") (pin "10") (pinfunction "BS2_10") (pintype "bidirectional"))
      (node (ref "OLED4") (pin "27") (pinfunction "VLSS_27") (pintype "bidirectional"))
      (node (ref "OLED4") (pin "28") (pinfunction "GND_28") (pintype "bidirectional"))
      (node (ref "OLED4") (pin "7") (pinfunction "VSS_7") (pintype "bidirectional"))
      (node (ref "OLED4") (pin "9") (pinfunction "BS1_9") (pintype "bidirectional"))
      (node (ref "OLED5") (pin "1") (pinfunction "GND_1") (pintype "bidirectional"))
      (node (ref "OLED5") (pin "10") (pinfunction "BS2_10") (pintype "bidirectional"))
      (node (ref "OLED5") (pin "27") (pinfunction "VLSS_27") (pintype "bidirectional"))
      (node (ref "OLED5") (pin "28") (pinfunction "GND_28") (pintype "bidirectional"))
      (node (ref "OLED5") (pin "7") (pinfunction "VSS_7") (pintype "bidirectional"))
      (node (ref "OLED5") (pin "9") (pinfunction "BS1_9") (pintype "bidirectional"))
      (node (ref "OLED6") (pin "1") (pinfunction "GND_1") (pintype "bidirectional"))
      (node (ref "OLED6") (pin "10") (pinfunction "BS2_10") (pintype "bidirectional"))
      (node (ref "OLED6") (pin "27") (pinfunction "VLSS_27") (pintype "bidirectional"))
      (node (ref "OLED6") (pin "28") (pinfunction "GND_28") (pintype "bidirectional"))
      (node (ref "OLED6") (pin "7") (pinfunction "VSS_7") (pintype "bidirectional"))
      (node (ref "OLED6") (pin "9") (pinfunction "BS1_9") (pintype "bidirectional"))
      (node (ref "OLED7") (pin "1") (pinfunction "GND_1") (pintype "bidirectional"))
      (node (ref "OLED7") (pin "10") (pinfunction "BS2_10") (pintype "bidirectional"))
      (node (ref "OLED7") (pin "27") (pinfunction "VLSS_27") (pintype "bidirectional"))
      (node (ref "OLED7") (pin "28") (pinfunction "GND_28") (pintype "bidirectional"))
      (node (ref "OLED7") (pin "7") (pinfunction "VSS_7") (pintype "bidirectional"))
      (node (ref "OLED7") (pin "9") (pinfunction "BS1_9") (pintype "bidirectional"))
      (node (ref "OLED8") (pin "1") (pinfunction "GND_1") (pintype "bidirectional"))
      (node (ref "OLED8") (pin "10") (pinfunction "BS2_10") (pintype "bidirectional"))
      (node (ref "OLED8") (pin "27") (pinfunction "VLSS_27") (pintype "bidirectional"))
      (node (ref "OLED8") (pin "28") (pinfunction "GND_28") (pintype "bidirectional"))
      (node (ref "OLED8") (pin "7") (pinfunction "VSS_7") (pintype "bidirectional"))
      (node (ref "OLED8") (pin "9") (pinfunction "BS1_9") (pintype "bidirectional"))
      (node (ref "OLED9") (pin "1") (pinfunction "GND_1") (pintype "bidirectional"))
      (node (ref "OLED9") (pin "10") (pinfunction "BS2_10") (pintype "bidirectional"))
      (node (ref "OLED9") (pin "27") (pinfunction "VLSS_27") (pintype "bidirectional"))
      (node (ref "OLED9") (pin "28") (pinfunction "GND_28") (pintype "bidirectional"))
      (node (ref "OLED9") (pin "7") (pinfunction "VSS_7") (pintype "bidirectional"))
      (node (ref "OLED9") (pin "9") (pinfunction "BS1_9") (pintype "bidirectional"))
      (node (ref "R1") (pin "2") (pinfunction "2_2") (pintype "passive"))
      (node (ref "R10") (pin "2") (pinfunction "2_2") (pintype "passive"))
      (node (ref "R11") (pin "2") (pinfunction "2_2") (pintype "passive"))
      (node (ref "R12") (pin "1") (pinfunction "1_1") (pintype "passive"))
      (node (ref "R15") (pin "1") (pinfunction "1_1") (pintype "passive"))
      (node (ref "R16") (pin "1") (pinfunction "1_1") (pintype "passive"))
      (node (ref "R19") (pin "2") (pinfunction "2_2") (pintype "passive"))
      (node (ref "R2") (pin "2") (pinfunction "2_2") (pintype "passive"))
      (node (ref "R21") (pin "2") (pinfunction "2_2") (pintype "passive"))
      (node (ref "R22") (pin "2") (pinfunction "2_2") (pintype "passive"))
      (node (ref "R23") (pin "2") (pinfunction "2_2") (pintype "passive"))
      (node (ref "R3") (pin "2") (pinfunction "2_2") (pintype "passive"))
      (node (ref "R4") (pin "2") (pinfunction "2_2") (pintype "passive"))
      (node (ref "R5") (pin "2") (pinfunction "2_2") (pintype "passive"))
      (node (ref "R6") (pin "2") (pinfunction "2_2") (pintype "passive"))
      (node (ref "R7") (pin "2") (pinfunction "2_2") (pintype "passive"))
      (node (ref "R9") (pin "2") (pinfunction "2_2") (pintype "passive"))
      (node (ref "SW1") (pin "B") (pinfunction "S_B") (pintype "passive"))
      (node (ref "SW1") (pin "B'") (pinfunction "S1_B'") (pintype "passive"))
      (node (ref "SW10") (pin "B") (pinfunction "S_B") (pintype "passive"))
      (node (ref "SW10") (pin "B'") (pinfunction "S1_B'") (pintype "passive"))
      (node (ref "SW11") (pin "B") (pinfunction "S_B") (pintype "passive"))
      (node (ref "SW11") (pin "B'") (pinfunction "S1_B'") (pintype "passive"))
      (node (ref "SW12") (pin "B") (pinfunction "S_B") (pintype "passive"))
      (node (ref "SW12") (pin "B'") (pinfunction "S1_B'") (pintype "passive"))
      (node (ref "SW2") (pin "B") (pinfunction "S_B") (pintype "passive"))
      (node (ref "SW2") (pin "B'") (pinfunction "S1_B'") (pintype "passive"))
      (node (ref "SW3") (pin "B") (pinfunction "S_B") (pintype "passive"))
      (node (ref "SW3") (pin "B'") (pinfunction "S1_B'") (pintype "passive"))
      (node (ref "SW4") (pin "B") (pinfunction "S_B") (pintype "passive"))
      (node (ref "SW4") (pin "B'") (pinfunction "S1_B'") (pintype "passive"))
      (node (ref "SW5") (pin "B") (pinfunction "S_B") (pintype "passive"))
      (node (ref "SW5") (pin "B'") (pinfunction "S1_B'") (pintype "passive"))
      (node (ref "SW6") (pin "B") (pinfunction "S_B") (pintype "passive"))
      (node (ref "SW6") (pin "B'") (pinfunction "S1_B'") (pintype "passive"))
      (node (ref "SW7") (pin "B") (pinfunction "S_B") (pintype "passive"))
      (node (ref "SW7") (pin "B'") (pinfunction "S1_B'") (pintype "passive"))
      (node (ref "SW8") (pin "B") (pinfunction "S_B") (pintype "passive"))
      (node (ref "SW8") (pin "B'") (pinfunction "S1_B'") (pintype "passive"))
      (node (ref "SW9") (pin "B") (pinfunction "S_B") (pintype "passive"))
      (node (ref "SW9") (pin "B'") (pinfunction "S1_B'") (pintype "passive"))
      (node (ref "TP3") (pin "P$1") (pinfunction "P$1_P$1") (pintype "bidirectional"))
      (node (ref "U3") (pin "2") (pinfunction "GND_2") (pintype "input"))
      (node (ref "UC1") (pin "23") (pinfunction "VSS_1_23") (pintype "power_in"))
      (node (ref "UC1") (pin "35") (pinfunction "VSS_2_35") (pintype "power_in"))
      (node (ref "UC1") (pin "47") (pinfunction "VSS_3_47") (pintype "power_in"))
      (node (ref "UC1") (pin "8") (pinfunction "VSS_A_8") (pintype "power_in"))
    )
    (net (code "22") (name "MOSI") (class "Default")
      (node (ref "OLED1") (pin "17") (pinfunction "D1/MOSI_17") (pintype "bidirectional"))
      (node (ref "OLED10") (pin "17") (pinfunction "D1/MOSI_17") (pintype "bidirectional"))
      (node (ref "OLED11") (pin "17") (pinfunction "D1/MOSI_17") (pintype "bidirectional"))
      (node (ref "OLED12") (pin "17") (pinfunction "D1/MOSI_17") (pintype "bidirectional"))
      (node (ref "OLED2") (pin "17") (pinfunction "D1/MOSI_17") (pintype "bidirectional"))
      (node (ref "OLED3") (pin "17") (pinfunction "D1/MOSI_17") (pintype "bidirectional"))
      (node (ref "OLED4") (pin "17") (pinfunction "D1/MOSI_17") (pintype "bidirectional"))
      (node (ref "OLED5") (pin "17") (pinfunction "D1/MOSI_17") (pintype "bidirectional"))
      (node (ref "OLED6") (pin "17") (pinfunction "D1/MOSI_17") (pintype "bidirectional"))
      (node (ref "OLED7") (pin "17") (pinfunction "D1/MOSI_17") (pintype "bidirectional"))
      (node (ref "OLED8") (pin "17") (pinfunction "D1/MOSI_17") (pintype "bidirectional"))
      (node (ref "OLED9") (pin "17") (pinfunction "D1/MOSI_17") (pintype "bidirectional"))
      (node (ref "UC1") (pin "17") (pinfunction "PA7/SPI1_MOSI/ADC12_IN7/TIM3_CH2_17") (pintype "bidirectional"))
    )
    (net (code "23") (name "Net-(F1-Pad1)") (class "Default")
      (node (ref "F1") (pin "1") (pinfunction "1_1") (pintype "bidirectional"))
      (node (ref "J2") (pin "VBUS1") (pinfunction "VBUS_VBUS1") (pintype "bidirectional"))
      (node (ref "J2") (pin "VBUS2") (pinfunction "VBUS_VBUS2") (pintype "bidirectional"))
    )
    (net (code "24") (name "Net-(J2-CC1)") (class "Default")
      (node (ref "J2") (pin "A5") (pinfunction "CC1_A5") (pintype "bidirectional"))
      (node (ref "R19") (pin "1") (pinfunction "1_1") (pintype "passive"))
    )
    (net (code "25") (name "Net-(J2-CC2)") (class "Default")
      (node (ref "J2") (pin "B5") (pinfunction "CC2_B5") (pintype "bidirectional"))
      (node (ref "R3") (pin "1") (pinfunction "1_1") (pintype "passive"))
    )
    (net (code "26") (name "Net-(OLED1-C1N)") (class "Default")
      (node (ref "C1") (pin "2") (pinfunction "2_2") (pintype "passive"))
      (node (ref "OLED1") (pin "5") (pinfunction "C1N_5") (pintype "bidirectional"))
    )
    (net (code "27") (name "Net-(OLED1-C1P)") (class "Default")
      (node (ref "C1") (pin "1") (pinfunction "1_1") (pintype "passive"))
      (node (ref "OLED1") (pin "4") (pinfunction "C1P_4") (pintype "bidirectional"))
    )
    (net (code "28") (name "Net-(OLED1-C2N)") (class "Default")
      (node (ref "C3") (pin "2") (pinfunction "2_2") (pintype "passive"))
      (node (ref "OLED1") (pin "3") (pinfunction "C2N_3") (pintype "bidirectional"))
    )
    (net (code "29") (name "Net-(OLED1-C2P)") (class "Default")
      (node (ref "C3") (pin "1") (pinfunction "1_1") (pintype "passive"))
      (node (ref "OLED1") (pin "2") (pinfunction "C2P_2") (pintype "bidirectional"))
    )
    (net (code "30") (name "Net-(OLED1-IREF)") (class "Default")
      (node (ref "OLED1") (pin "24") (pinfunction "IREF_24") (pintype "bidirectional"))
      (node (ref "R1") (pin "1") (pinfunction "1_1") (pintype "passive"))
    )
    (net (code "31") (name "Net-(OLED1-VCC)") (class "Default")
      (node (ref "C4") (pin "1") (pinfunction "1_1") (pintype "passive"))
      (node (ref "OLED1") (pin "26") (pinfunction "VCC_26") (pintype "bidirectional"))
    )
    (net (code "32") (name "Net-(OLED1-VCOMH)") (class "Default")
      (node (ref "C5") (pin "1") (pinfunction "1_1") (pintype "passive"))
      (node (ref "OLED1") (pin "25") (pinfunction "VCOMH_25") (pintype "bidirectional"))
    )
    (net (code "33") (name "Net-(OLED2-C1N)") (class "Default")
      (node (ref "C19") (pin "2") (pinfunction "2_2") (pintype "passive"))
      (node (ref "OLED2") (pin "5") (pinfunction "C1N_5") (pintype "bidirectional"))
    )
    (net (code "34") (name "Net-(OLED2-C1P)") (class "Default")
      (node (ref "C19") (pin "1") (pinfunction "1_1") (pintype "passive"))
      (node (ref "OLED2") (pin "4") (pinfunction "C1P_4") (pintype "bidirectional"))
    )
    (net (code "35") (name "Net-(OLED2-C2N)") (class "Default")
      (node (ref "C18") (pin "2") (pinfunction "2_2") (pintype "passive"))
      (node (ref "OLED2") (pin "3") (pinfunction "C2N_3") (pintype "bidirectional"))
    )
    (net (code "36") (name "Net-(OLED2-C2P)") (class "Default")
      (node (ref "C18") (pin "1") (pinfunction "1_1") (pintype "passive"))
      (node (ref "OLED2") (pin "2") (pinfunction "C2P_2") (pintype "bidirectional"))
    )
    (net (code "37") (name "Net-(OLED2-IREF)") (class "Default")
      (node (ref "OLED2") (pin "24") (pinfunction "IREF_24") (pintype "bidirectional"))
      (node (ref "R2") (pin "1") (pinfunction "1_1") (pintype "passive"))
    )
    (net (code "38") (name "Net-(OLED2-VCC)") (class "Default")
      (node (ref "C17") (pin "1") (pinfunction "1_1") (pintype "passive"))
      (node (ref "OLED2") (pin "26") (pinfunction "VCC_26") (pintype "bidirectional"))
    )
    (net (code "39") (name "Net-(OLED2-VCOMH)") (class "Default")
      (node (ref "C16") (pin "1") (pinfunction "1_1") (pintype "passive"))
      (node (ref "OLED2") (pin "25") (pinfunction "VCOMH_25") (pintype "bidirectional"))
    )
    (net (code "40") (name "Net-(OLED3-C1N)") (class "Default")
      (node (ref "C24") (pin "2") (pinfunction "2_2") (pintype "passive"))
      (node (ref "OLED3") (pin "5") (pinfunction "C1N_5") (pintype "bidirectional"))
    )
    (net (code "41") (name "Net-(OLED3-C1P)") (class "Default")
      (node (ref "C24") (pin "1") (pinfunction "1_1") (pintype "passive"))
      (node (ref "OLED3") (pin "4") (pinfunction "C1P_4") (pintype "bidirectional"))
    )
    (net (code "42") (name "Net-(OLED3-C2N)") (class "Default")
      (node (ref "C23") (pin "2") (pinfunction "2_2") (pintype "passive"))
      (node (ref "OLED3") (pin "3") (pinfunction "C2N_3") (pintype "bidirectional"))
    )
    (net (code "43") (name "Net-(OLED3-C2P)") (class "Default")
      (node (ref "C23") (pin "1") (pinfunction "1_1") (pintype "passive"))
      (node (ref "OLED3") (pin "2") (pinfunction "C2P_2") (pintype "bidirectional"))
    )
    (net (code "44") (name "Net-(OLED3-IREF)") (class "Default")
      (node (ref "OLED3") (pin "24") (pinfunction "IREF_24") (pintype "bidirectional"))
      (node (ref "R4") (pin "1") (pinfunction "1_1") (pintype "passive"))
    )
    (net (code "45") (name "Net-(OLED3-VCC)") (class "Default")
      (node (ref "C22") (pin "1") (pinfunction "1_1") (pintype "passive"))
      (node (ref "OLED3") (pin "26") (pinfunction "VCC_26") (pintype "bidirectional"))
    )
    (net (code "46") (name "Net-(OLED3-VCOMH)") (class "Default")
      (node (ref "C21") (pin "1") (pinfunction "1_1") (pintype "passive"))
      (node (ref "OLED3") (pin "25") (pinfunction "VCOMH_25") (pintype "bidirectional"))
    )
    (net (code "47") (name "Net-(OLED4-C1N)") (class "Default")
      (node (ref "C29") (pin "2") (pinfunction "2_2") (pintype "passive"))
      (node (ref "OLED4") (pin "5") (pinfunction "C1N_5") (pintype "bidirectional"))
    )
    (net (code "48") (name "Net-(OLED4-C1P)") (class "Default")
      (node (ref "C29") (pin "1") (pinfunction "1_1") (pintype "passive"))
      (node (ref "OLED4") (pin "4") (pinfunction "C1P_4") (pintype "bidirectional"))
    )
    (net (code "49") (name "Net-(OLED4-C2N)") (class "Default")
      (node (ref "C28") (pin "2") (pinfunction "2_2") (pintype "passive"))
      (node (ref "OLED4") (pin "3") (pinfunction "C2N_3") (pintype "bidirectional"))
    )
    (net (code "50") (name "Net-(OLED4-C2P)") (class "Default")
      (node (ref "C28") (pin "1") (pinfunction "1_1") (pintype "passive"))
      (node (ref "OLED4") (pin "2") (pinfunction "C2P_2") (pintype "bidirectional"))
    )
    (net (code "51") (name "Net-(OLED4-IREF)") (class "Default")
      (node (ref "OLED4") (pin "24") (pinfunction "IREF_24") (pintype "bidirectional"))
      (node (ref "R5") (pin "1") (pinfunction "1_1") (pintype "passive"))
    )
    (net (code "52") (name "Net-(OLED4-VCC)") (class "Default")
      (node (ref "C27") (pin "1") (pinfunction "1_1") (pintype "passive"))
      (node (ref "OLED4") (pin "26") (pinfunction "VCC_26") (pintype "bidirectional"))
    )
    (net (code "53") (name "Net-(OLED4-VCOMH)") (class "Default")
      (node (ref "C26") (pin "1") (pinfunction "1_1") (pintype "passive"))
      (node (ref "OLED4") (pin "25") (pinfunction "VCOMH_25") (pintype "bidirectional"))
    )
    (net (code "54") (name "Net-(OLED5-C1N)") (class "Default")
      (node (ref "C34") (pin "2") (pinfunction "2_2") (pintype "passive"))
      (node (ref "OLED5") (pin "5") (pinfunction "C1N_5") (pintype "bidirectional"))
    )
    (net (code "55") (name "Net-(OLED5-C1P)") (class "Default")
      (node (ref "C34") (pin "1") (pinfunction "1_1") (pintype "passive"))
      (node (ref "OLED5") (pin "4") (pinfunction "C1P_4") (pintype "bidirectional"))
    )
    (net (code "56") (name "Net-(OLED5-C2N)") (class "Default")
      (node (ref "C33") (pin "2") (pinfunction "2_2") (pintype "passive"))
      (node (ref "OLED5") (pin "3") (pinfunction "C2N_3") (pintype "bidirectional"))
    )
    (net (code "57") (name "Net-(OLED5-C2P)") (class "Default")
      (node (ref "C33") (pin "1") (pinfunction "1_1") (pintype "passive"))
      (node (ref "OLED5") (pin "2") (pinfunction "C2P_2") (pintype "bidirectional"))
    )
    (net (code "58") (name "Net-(OLED5-IREF)") (class "Default")
      (node (ref "OLED5") (pin "24") (pinfunction "IREF_24") (pintype "bidirectional"))
      (node (ref "R6") (pin "1") (pinfunction "1_1") (pintype "passive"))
    )
    (net (code "59") (name "Net-(OLED5-VCC)") (class "Default")
      (node (ref "C32") (pin "1") (pinfunction "1_1") (pintype "passive"))
      (node (ref "OLED5") (pin "26") (pinfunction "VCC_26") (pintype "bidirectional"))
    )
    (net (code "60") (name "Net-(OLED5-VCOMH)") (class "Default")
      (node (ref "C31") (pin "1") (pinfunction "1_1") (pintype "passive"))
      (node (ref "OLED5") (pin "25") (pinfunction "VCOMH_25") (pintype "bidirectional"))
    )
    (net (code "61") (name "Net-(OLED6-C1N)") (class "Default")
      (node (ref "C39") (pin "2") (pinfunction "2_2") (pintype "passive"))
      (node (ref "OLED6") (pin "5") (pinfunction "C1N_5") (pintype "bidirectional"))
    )
    (net (code "62") (name "Net-(OLED6-C1P)") (class "Default")
      (node (ref "C39") (pin "1") (pinfunction "1_1") (pintype "passive"))
      (node (ref "OLED6") (pin "4") (pinfunction "C1P_4") (pintype "bidirectional"))
    )
    (net (code "63") (name "Net-(OLED6-C2N)") (class "Default")
      (node (ref "C38") (pin "2") (pinfunction "2_2") (pintype "passive"))
      (node (ref "OLED6") (pin "3") (pinfunction "C2N_3") (pintype "bidirectional"))
    )
    (net (code "64") (name "Net-(OLED6-C2P)") (class "Default")
      (node (ref "C38") (pin "1") (pinfunction "1_1") (pintype "passive"))
      (node (ref "OLED6") (pin "2") (pinfunction "C2P_2") (pintype "bidirectional"))
    )
    (net (code "65") (name "Net-(OLED6-IREF)") (class "Default")
      (node (ref "OLED6") (pin "24") (pinfunction "IREF_24") (pintype "bidirectional"))
      (node (ref "R7") (pin "1") (pinfunction "1_1") (pintype "passive"))
    )
    (net (code "66") (name "Net-(OLED6-VCC)") (class "Default")
      (node (ref "C37") (pin "1") (pinfunction "1_1") (pintype "passive"))
      (node (ref "OLED6") (pin "26") (pinfunction "VCC_26") (pintype "bidirectional"))
    )
    (net (code "67") (name "Net-(OLED6-VCOMH)") (class "Default")
      (node (ref "C36") (pin "1") (pinfunction "1_1") (pintype "passive"))
      (node (ref "OLED6") (pin "25") (pinfunction "VCOMH_25") (pintype "bidirectional"))
    )
    (net (code "68") (name "Net-(OLED7-C1N)") (class "Default")
      (node (ref "C44") (pin "2") (pinfunction "2_2") (pintype "passive"))
      (node (ref "OLED7") (pin "5") (pinfunction "C1N_5") (pintype "bidirectional"))
    )
    (net (code "69") (name "Net-(OLED7-C1P)") (class "Default")
      (node (ref "C44") (pin "1") (pinfunction "1_1") (pintype "passive"))
      (node (ref "OLED7") (pin "4") (pinfunction "C1P_4") (pintype "bidirectional"))
    )
    (net (code "70") (name "Net-(OLED7-C2N)") (class "Default")
      (node (ref "C43") (pin "2") (pinfunction "2_2") (pintype "passive"))
      (node (ref "OLED7") (pin "3") (pinfunction "C2N_3") (pintype "bidirectional"))
    )
    (net (code "71") (name "Net-(OLED7-C2P)") (class "Default")
      (node (ref "C43") (pin "1") (pinfunction "1_1") (pintype "passive"))
      (node (ref "OLED7") (pin "2") (pinfunction "C2P_2") (pintype "bidirectional"))
    )
    (net (code "72") (name "Net-(OLED7-IREF)") (class "Default")
      (node (ref "OLED7") (pin "24") (pinfunction "IREF_24") (pintype "bidirectional"))
      (node (ref "R9") (pin "1") (pinfunction "1_1") (pintype "passive"))
    )
    (net (code "73") (name "Net-(OLED7-VCC)") (class "Default")
      (node (ref "C42") (pin "1") (pinfunction "1_1") (pintype "passive"))
      (node (ref "OLED7") (pin "26") (pinfunction "VCC_26") (pintype "bidirectional"))
    )
    (net (code "74") (name "Net-(OLED7-VCOMH)") (class "Default")
      (node (ref "C41") (pin "1") (pinfunction "1_1") (pintype "passive"))
      (node (ref "OLED7") (pin "25") (pinfunction "VCOMH_25") (pintype "bidirectional"))
    )
    (net (code "75") (name "Net-(OLED8-C1N)") (class "Default")
      (node (ref "C49") (pin "2") (pinfunction "2_2") (pintype "passive"))
      (node (ref "OLED8") (pin "5") (pinfunction "C1N_5") (pintype "bidirectional"))
    )
    (net (code "76") (name "Net-(OLED8-C1P)") (class "Default")
      (node (ref "C49") (pin "1") (pinfunction "1_1") (pintype "passive"))
      (node (ref "OLED8") (pin "4") (pinfunction "C1P_4") (pintype "bidirectional"))
    )
    (net (code "77") (name "Net-(OLED8-C2N)") (class "Default")
      (node (ref "C48") (pin "2") (pinfunction "2_2") (pintype "passive"))
      (node (ref "OLED8") (pin "3") (pinfunction "C2N_3") (pintype "bidirectional"))
    )
    (net (code "78") (name "Net-(OLED8-C2P)") (class "Default")
      (node (ref "C48") (pin "1") (pinfunction "1_1") (pintype "passive"))
      (node (ref "OLED8") (pin "2") (pinfunction "C2P_2") (pintype "bidirectional"))
    )
    (net (code "79") (name "Net-(OLED8-IREF)") (class "Default")
      (node (ref "OLED8") (pin "24") (pinfunction "IREF_24") (pintype "bidirectional"))
      (node (ref "R10") (pin "1") (pinfunction "1_1") (pintype "passive"))
    )
    (net (code "80") (name "Net-(OLED8-VCC)") (class "Default")
      (node (ref "C47") (pin "1") (pinfunction "1_1") (pintype "passive"))
      (node (ref "OLED8") (pin "26") (pinfunction "VCC_26") (pintype "bidirectional"))
    )
    (net (code "81") (name "Net-(OLED8-VCOMH)") (class "Default")
      (node (ref "C46") (pin "1") (pinfunction "1_1") (pintype "passive"))
      (node (ref "OLED8") (pin "25") (pinfunction "VCOMH_25") (pintype "bidirectional"))
    )
    (net (code "82") (name "Net-(OLED9-C1N)") (class "Default")
      (node (ref "C54") (pin "2") (pinfunction "2_2") (pintype "passive"))
      (node (ref "OLED9") (pin "5") (pinfunction "C1N_5") (pintype "bidirectional"))
    )
    (net (code "83") (name "Net-(OLED9-C1P)") (class "Default")
      (node (ref "C54") (pin "1") (pinfunction "1_1") (pintype "passive"))
      (node (ref "OLED9") (pin "4") (pinfunction "C1P_4") (pintype "bidirectional"))
    )
    (net (code "84") (name "Net-(OLED9-C2N)") (class "Default")
      (node (ref "C53") (pin "2") (pinfunction "2_2") (pintype "passive"))
      (node (ref "OLED9") (pin "3") (pinfunction "C2N_3") (pintype "bidirectional"))
    )
    (net (code "85") (name "Net-(OLED9-C2P)") (class "Default")
      (node (ref "C53") (pin "1") (pinfunction "1_1") (pintype "passive"))
      (node (ref "OLED9") (pin "2") (pinfunction "C2P_2") (pintype "bidirectional"))
    )
    (net (code "86") (name "Net-(OLED9-IREF)") (class "Default")
      (node (ref "OLED9") (pin "24") (pinfunction "IREF_24") (pintype "bidirectional"))
      (node (ref "R11") (pin "1") (pinfunction "1_1") (pintype "passive"))
    )
    (net (code "87") (name "Net-(OLED9-VCC)") (class "Default")
      (node (ref "C52") (pin "1") (pinfunction "1_1") (pintype "passive"))
      (node (ref "OLED9") (pin "26") (pinfunction "VCC_26") (pintype "bidirectional"))
    )
    (net (code "88") (name "Net-(OLED9-VCOMH)") (class "Default")
      (node (ref "C51") (pin "1") (pinfunction "1_1") (pintype "passive"))
      (node (ref "OLED9") (pin "25") (pinfunction "VCOMH_25") (pintype "bidirectional"))
    )
    (net (code "89") (name "Net-(OLED10-C1N)") (class "Default")
      (node (ref "C59") (pin "2") (pinfunction "2_2") (pintype "passive"))
      (node (ref "OLED10") (pin "5") (pinfunction "C1N_5") (pintype "bidirectional"))
    )
    (net (code "90") (name "Net-(OLED10-C1P)") (class "Default")
      (node (ref "C59") (pin "1") (pinfunction "1_1") (pintype "passive"))
      (node (ref "OLED10") (pin "4") (pinfunction "C1P_4") (pintype "bidirectional"))
    )
    (net (code "91") (name "Net-(OLED10-C2N)") (class "Default")
      (node (ref "C58") (pin "2") (pinfunction "2_2") (pintype "passive"))
      (node (ref "OLED10") (pin "3") (pinfunction "C2N_3") (pintype "bidirectional"))
    )
    (net (code "92") (name "Net-(OLED10-C2P)") (class "Default")
      (node (ref "C58") (pin "1") (pinfunction "1_1") (pintype "passive"))
      (node (ref "OLED10") (pin "2") (pinfunction "C2P_2") (pintype "bidirectional"))
    )
    (net (code "93") (name "Net-(OLED10-IREF)") (class "Default")
      (node (ref "OLED10") (pin "24") (pinfunction "IREF_24") (pintype "bidirectional"))
      (node (ref "R21") (pin "1") (pinfunction "1_1") (pintype "passive"))
    )
    (net (code "94") (name "Net-(OLED10-VCC)") (class "Default")
      (node (ref "C57") (pin "1") (pinfunction "1_1") (pintype "passive"))
      (node (ref "OLED10") (pin "26") (pinfunction "VCC_26") (pintype "bidirectional"))
    )
    (net (code "95") (name "Net-(OLED10-VCOMH)") (class "Default")
      (node (ref "C56") (pin "1") (pinfunction "1_1") (pintype "passive"))
      (node (ref "OLED10") (pin "25") (pinfunction "VCOMH_25") (pintype "bidirectional"))
    )
    (net (code "96") (name "Net-(OLED11-C1N)") (class "Default")
      (node (ref "C64") (pin "2") (pinfunction "2_2") (pintype "passive"))
      (node (ref "OLED11") (pin "5") (pinfunction "C1N_5") (pintype "bidirectional"))
    )
    (net (code "97") (name "Net-(OLED11-C1P)") (class "Default")
      (node (ref "C64") (pin "1") (pinfunction "1_1") (pintype "passive"))
      (node (ref "OLED11") (pin "4") (pinfunction "C1P_4") (pintype "bidirectional"))
    )
    (net (code "98") (name "Net-(OLED11-C2N)") (class "Default")
      (node (ref "C63") (pin "2") (pinfunction "2_2") (pintype "passive"))
      (node (ref "OLED11") (pin "3") (pinfunction "C2N_3") (pintype "bidirectional"))
    )
    (net (code "99") (name "Net-(OLED11-C2P)") (class "Default")
      (node (ref "C63") (pin "1") (pinfunction "1_1") (pintype "passive"))
      (node (ref "OLED11") (pin "2") (pinfunction "C2P_2") (pintype "bidirectional"))
    )
    (net (code "100") (name "Net-(OLED11-IREF)") (class "Default")
      (node (ref "OLED11") (pin "24") (pinfunction "IREF_24") (pintype "bidirectional"))
      (node (ref "R22") (pin "1") (pinfunction "1_1") (pintype "passive"))
    )
    (net (code "101") (name "Net-(OLED11-VCC)") (class "Default")
      (node (ref "C62") (pin "1") (pinfunction "1_1") (pintype "passive"))
      (node (ref "OLED11") (pin "26") (pinfunction "VCC_26") (pintype "bidirectional"))
    )
    (net (code "102") (name "Net-(OLED11-VCOMH)") (class "Default")
      (node (ref "C61") (pin "1") (pinfunction "1_1") (pintype "passive"))
      (node (ref "OLED11") (pin "25") (pinfunction "VCOMH_25") (pintype "bidirectional"))
    )
    (net (code "103") (name "Net-(OLED12-C1N)") (class "Default")
      (node (ref "C69") (pin "2") (pinfunction "2_2") (pintype "passive"))
      (node (ref "OLED12") (pin "5") (pinfunction "C1N_5") (pintype "bidirectional"))
    )
    (net (code "104") (name "Net-(OLED12-C1P)") (class "Default")
      (node (ref "C69") (pin "1") (pinfunction "1_1") (pintype "passive"))
      (node (ref "OLED12") (pin "4") (pinfunction "C1P_4") (pintype "bidirectional"))
    )
    (net (code "105") (name "Net-(OLED12-C2N)") (class "Default")
      (node (ref "C68") (pin "2") (pinfunction "2_2") (pintype "passive"))
      (node (ref "OLED12") (pin "3") (pinfunction "C2N_3") (pintype "bidirectional"))
    )
    (net (code "106") (name "Net-(OLED12-C2P)") (class "Default")
      (node (ref "C68") (pin "1") (pinfunction "1_1") (pintype "passive"))
      (node (ref "OLED12") (pin "2") (pinfunction "C2P_2") (pintype "bidirectional"))
    )
    (net (code "107") (name "Net-(OLED12-IREF)") (class "Default")
      (node (ref "OLED12") (pin "24") (pinfunction "IREF_24") (pintype "bidirectional"))
      (node (ref "R23") (pin "1") (pinfunction "1_1") (pintype "passive"))
    )
    (net (code "108") (name "Net-(OLED12-VCC)") (class "Default")
      (node (ref "C67") (pin "1") (pinfunction "1_1") (pintype "passive"))
      (node (ref "OLED12") (pin "26") (pinfunction "VCC_26") (pintype "bidirectional"))
    )
    (net (code "109") (name "Net-(OLED12-VCOMH)") (class "Default")
      (node (ref "C66") (pin "1") (pinfunction "1_1") (pintype "passive"))
      (node (ref "OLED12") (pin "25") (pinfunction "VCOMH_25") (pintype "bidirectional"))
    )
    (net (code "110") (name "Net-(R17-Pad1)") (class "Default")
      (node (ref "R17") (pin "1") (pinfunction "1_1") (pintype "passive"))
      (node (ref "SJ1") (pin "2") (pinfunction "2_2") (pintype "passive"))
    )
    (net (code "111") (name "Net-(R18-Pad1)") (class "Default")
      (node (ref "R18") (pin "1") (pinfunction "1_1") (pintype "passive"))
      (node (ref "SJ2") (pin "2") (pinfunction "2_2") (pintype "passive"))
    )
    (net (code "112") (name "Net-(SW13-S)") (class "Default")
      (node (ref "R16") (pin "2") (pinfunction "2_2") (pintype "passive"))
      (node (ref "SW13") (pin "B") (pinfunction "S_B") (pintype "passive"))
      (node (ref "SW13") (pin "B'") (pinfunction "S1_B'") (pintype "passive"))
    )
    (net (code "113") (name "OSC_IN") (class "Default")
      (node (ref "C6") (pin "2") (pinfunction "2_2") (pintype "passive"))
      (node (ref "OSC") (pin "1") (pinfunction "1_1") (pintype "passive"))
      (node (ref "UC1") (pin "5") (pinfunction "PD0-OSC_IN_5") (pintype "input"))
    )
    (net (code "114") (name "OSC_OUT") (class "Default")
      (node (ref "C7") (pin "2") (pinfunction "2_2") (pintype "passive"))
      (node (ref "OSC") (pin "3") (pinfunction "2_3") (pintype "passive"))
      (node (ref "UC1") (pin "6") (pinfunction "PD1-OSC_OUT_6") (pintype "input"))
    )
    (net (code "115") (name "RESET") (class "Default")
      (node (ref "R8") (pin "1") (pinfunction "1_1") (pintype "passive"))
      (node (ref "SW13") (pin "A") (pinfunction "P_A") (pintype "passive"))
      (node (ref "SW13") (pin "A'") (pinfunction "P1_A'") (pintype "passive"))
      (node (ref "UC1") (pin "7") (pinfunction "NRST_7") (pintype "input"))
    )
    (net (code "116") (name "SCK") (class "Default")
      (node (ref "OLED1") (pin "16") (pinfunction "D0/SCK_16") (pintype "bidirectional"))
      (node (ref "OLED10") (pin "16") (pinfunction "D0/SCK_16") (pintype "bidirectional"))
      (node (ref "OLED11") (pin "16") (pinfunction "D0/SCK_16") (pintype "bidirectional"))
      (node (ref "OLED12") (pin "16") (pinfunction "D0/SCK_16") (pintype "bidirectional"))
      (node (ref "OLED2") (pin "16") (pinfunction "D0/SCK_16") (pintype "bidirectional"))
      (node (ref "OLED3") (pin "16") (pinfunction "D0/SCK_16") (pintype "bidirectional"))
      (node (ref "OLED4") (pin "16") (pinfunction "D0/SCK_16") (pintype "bidirectional"))
      (node (ref "OLED5") (pin "16") (pinfunction "D0/SCK_16") (pintype "bidirectional"))
      (node (ref "OLED6") (pin "16") (pinfunction "D0/SCK_16") (pintype "bidirectional"))
      (node (ref "OLED7") (pin "16") (pinfunction "D0/SCK_16") (pintype "bidirectional"))
      (node (ref "OLED8") (pin "16") (pinfunction "D0/SCK_16") (pintype "bidirectional"))
      (node (ref "OLED9") (pin "16") (pinfunction "D0/SCK_16") (pintype "bidirectional"))
      (node (ref "UC1") (pin "15") (pinfunction "PA5/SPI1_SCK/ADC12_IN5_15") (pintype "bidirectional"))
    )
    (net (code "117") (name "SW01") (class "Default")
      (node (ref "SW1") (pin "A") (pinfunction "P_A") (pintype "passive"))
      (node (ref "SW1") (pin "A'") (pinfunction "P1_A'") (pintype "passive"))
      (node (ref "UC1") (pin "13") (pinfunction "PA3/USART2_RX/ADC12_IN3/TIM2_CH4_13") (pintype "bidirectional"))
    )
    (net (code "118") (name "SW02") (class "Default")
      (node (ref "SW2") (pin "A") (pinfunction "P_A") (pintype "passive"))
      (node (ref "UC1") (pin "18") (pinfunction "PB0/ADC12_IN8/TIM3_CH3_18") (pintype "bidirectional"))
    )
    (net (code "119") (name "SW03") (class "Default")
      (node (ref "SW3") (pin "A") (pinfunction "P_A") (pintype "passive"))
      (node (ref "SW3") (pin "A'") (pinfunction "P1_A'") (pintype "passive"))
      (node (ref "UC1") (pin "25") (pinfunction "PB12/SPI2_NSS/I2C2_SMBA/USART3_CK/TIM1_BKIN_25") (pintype "input"))
    )
    (net (code "120") (name "SW04") (class "Default")
      (node (ref "SW4") (pin "A") (pinfunction "P_A") (pintype "passive"))
      (node (ref "SW4") (pin "A'") (pinfunction "P1_A'") (pintype "passive"))
      (node (ref "UC1") (pin "38") (pinfunction "PA15/JTDI_38") (pintype "bidirectional"))
    )
    (net (code "121") (name "SW05") (class "Default")
      (node (ref "SW5") (pin "A") (pinfunction "P_A") (pintype "passive"))
      (node (ref "SW5") (pin "A'") (pinfunction "P1_A'") (pintype "passive"))
      (node (ref "UC1") (pin "22") (pinfunction "PB11/I2C2_SDA/USART3_RX_22") (pintype "input"))
    )
    (net (code "122") (name "SW06") (class "Default")
      (node (ref "SW6") (pin "A") (pinfunction "P_A") (pintype "passive"))
      (node (ref "SW6") (pin "A'") (pinfunction "P1_A'") (pintype "passive"))
      (node (ref "TP1") (pin "P$1") (pinfunction "P$1_P$1") (pintype "bidirectional"))
      (node (ref "UC1") (pin "30") (pinfunction "PA9/USART1_TX/TIM1_CH2_30") (pintype "input"))
    )
    (net (code "123") (name "SW07") (class "Default")
      (node (ref "SW7") (pin "A") (pinfunction "P_A") (pintype "passive"))
      (node (ref "SW7") (pin "A'") (pinfunction "P1_A'") (pintype "passive"))
      (node (ref "UC1") (pin "37") (pinfunction "PA14/JTCK/SWCLK_37") (pintype "bidirectional"))
    )
    (net (code "124") (name "SW08") (class "Default")
      (node (ref "SW8") (pin "A") (pinfunction "P_A") (pintype "passive"))
      (node (ref "SW8") (pin "A'") (pinfunction "P1_A'") (pintype "passive"))
      (node (ref "UC1") (pin "21") (pinfunction "PB10/I2C2_SCL/USART3_TX_21") (pintype "input"))
    )
    (net (code "125") (name "SW09") (class "Default")
      (node (ref "SW9") (pin "A") (pinfunction "P_A") (pintype "passive"))
      (node (ref "SW9") (pin "A'") (pinfunction "P1_A'") (pintype "passive"))
      (node (ref "UC1") (pin "29") (pinfunction "PA8/USART1_CK/TIM1_CH1/MCO_29") (pintype "bidirectional"))
    )
    (net (code "126") (name "SW10") (class "Default")
      (node (ref "SW10") (pin "A") (pinfunction "P_A") (pintype "passive"))
      (node (ref "SW10") (pin "A'") (pinfunction "P1_A'") (pintype "passive"))
      (node (ref "UC1") (pin "42") (pinfunction "PB6/I2C1_SCL/TIM4_CH1_42") (pintype "input"))
    )
    (net (code "127") (name "SW11") (class "Default")
      (node (ref "SW11") (pin "A") (pinfunction "P_A") (pintype "passive"))
      (node (ref "SW11") (pin "A'") (pinfunction "P1_A'") (pintype "passive"))
      (node (ref "UC1") (pin "3") (pinfunction "PC14-OSC32_IN_3") (pintype "input"))
    )
    (net (code "128") (name "SW12") (class "Default")
      (node (ref "SW12") (pin "A") (pinfunction "P_A") (pintype "passive"))
      (node (ref "SW12") (pin "A'") (pinfunction "P1_A'") (pintype "passive"))
      (node (ref "UC1") (pin "45") (pinfunction "PB8/TIM4_CH3_45") (pintype "bidirectional"))
    )
    (net (code "129") (name "UART1_RX") (class "Default")
      (node (ref "TP2") (pin "P$1") (pinfunction "P$1_P$1") (pintype "bidirectional"))
      (node (ref "UC1") (pin "31") (pinfunction "PA10/USART1_RX/TIM1_CH3_31") (pintype "bidirectional"))
    )
    (net (code "130") (name "USBDM") (class "Default")
      (node (ref "C12") (pin "1") (pinfunction "1_1") (pintype "passive"))
      (node (ref "R14") (pin "2") (pinfunction "2_2") (pintype "passive"))
      (node (ref "UC1") (pin "32") (pinfunction "PA11/USART1_CTS/CAN_RX/TIM1_CH4/USBDM_32") (pintype "bidirectional"))
    )
    (net (code "131") (name "USBDP") (class "Default")
      (node (ref "C13") (pin "1") (pinfunction "1_1") (pintype "passive"))
      (node (ref "R13") (pin "2") (pinfunction "2_2") (pintype "passive"))
      (node (ref "R20") (pin "1") (pinfunction "1_1") (pintype "passive"))
      (node (ref "UC1") (pin "33") (pinfunction "PA12/USART1_RTS/CAN_TX/TIM1_ETR/USBDP_33") (pintype "bidirectional"))
    )
    (net (code "132") (name "V_USB") (class "Default")
      (node (ref "C8") (pin "1") (pinfunction "1_1") (pintype "passive"))
      (node (ref "F1") (pin "2") (pinfunction "2_2") (pintype "bidirectional"))
      (node (ref "U3") (pin "1") (pinfunction "IN_1") (pintype "input"))
      (node (ref "U3") (pin "3") (pinfunction "EN_3") (pintype "input"))
    )
    (net (code "133") (name "unconnected-(OLED1-D2-Pad18)") (class "Default")
      (node (ref "OLED1") (pin "18") (pinfunction "D2_18") (pintype "bidirectional"))
    )
    (net (code "134") (name "unconnected-(OLED1-D3-Pad19)") (class "Default")
      (node (ref "OLED1") (pin "19") (pinfunction "D3_19") (pintype "bidirectional"))
    )
    (net (code "135") (name "unconnected-(OLED1-D4-Pad20)") (class "Default")
      (node (ref "OLED1") (pin "20") (pinfunction "D4_20") (pintype "bidirectional"))
    )
    (net (code "136") (name "unconnected-(OLED1-D5-Pad21)") (class "Default")
      (node (ref "OLED1") (pin "21") (pinfunction "D5_21") (pintype "bidirectional"))
    )
    (net (code "137") (name "unconnected-(OLED1-D6-Pad22)") (class "Default")
      (node (ref "OLED1") (pin "22") (pinfunction "D6_22") (pintype "bidirectional"))
    )
    (net (code "138") (name "unconnected-(OLED1-D7-Pad23)") (class "Default")
      (node (ref "OLED1") (pin "23") (pinfunction "D7_23") (pintype "bidirectional"))
    )
    (net (code "139") (name "unconnected-(OLED1-E{slash}~{RD}-Pad15)") (class "Default")
      (node (ref "OLED1") (pin "15") (pinfunction "E/~{RD}_15") (pintype "bidirectional"))
    )
    (net (code "140") (name "unconnected-(OLED1-R{slash}~{W}-Pad14)") (class "Default")
      (node (ref "OLED1") (pin "14") (pinfunction "R/~{W}_14") (pintype "bidirectional"))
    )
    (net (code "141") (name "unconnected-(OLED2-D2-Pad18)") (class "Default")
      (node (ref "OLED2") (pin "18") (pinfunction "D2_18") (pintype "bidirectional"))
    )
    (net (code "142") (name "unconnected-(OLED2-D3-Pad19)") (class "Default")
      (node (ref "OLED2") (pin "19") (pinfunction "D3_19") (pintype "bidirectional"))
    )
    (net (code "143") (name "unconnected-(OLED2-D4-Pad20)") (class "Default")
      (node (ref "OLED2") (pin "20") (pinfunction "D4_20") (pintype "bidirectional"))
    )
    (net (code "144") (name "unconnected-(OLED2-D5-Pad21)") (class "Default")
      (node (ref "OLED2") (pin "21") (pinfunction "D5_21") (pintype "bidirectional"))
    )
    (net (code "145") (name "unconnected-(OLED2-D6-Pad22)") (class "Default")
      (node (ref "OLED2") (pin "22") (pinfunction "D6_22") (pintype "bidirectional"))
    )
    (net (code "146") (name "unconnected-(OLED2-D7-Pad23)") (class "Default")
      (node (ref "OLED2") (pin "23") (pinfunction "D7_23") (pintype "bidirectional"))
    )
    (net (code "147") (name "unconnected-(OLED2-E{slash}~{RD}-Pad15)") (class "Default")
      (node (ref "OLED2") (pin "15") (pinfunction "E/~{RD}_15") (pintype "bidirectional"))
    )
    (net (code "148") (name "unconnected-(OLED2-R{slash}~{W}-Pad14)") (class "Default")
      (node (ref "OLED2") (pin "14") (pinfunction "R/~{W}_14") (pintype "bidirectional"))
    )
    (net (code "149") (name "unconnected-(OLED3-D2-Pad18)") (class "Default")
      (node (ref "OLED3") (pin "18") (pinfunction "D2_18") (pintype "bidirectional"))
    )
    (net (code "150") (name "unconnected-(OLED3-D3-Pad19)") (class "Default")
      (node (ref "OLED3") (pin "19") (pinfunction "D3_19") (pintype "bidirectional"))
    )
    (net (code "151") (name "unconnected-(OLED3-D4-Pad20)") (class "Default")
      (node (ref "OLED3") (pin "20") (pinfunction "D4_20") (pintype "bidirectional"))
    )
    (net (code "152") (name "unconnected-(OLED3-D5-Pad21)") (class "Default")
      (node (ref "OLED3") (pin "21") (pinfunction "D5_21") (pintype "bidirectional"))
    )
    (net (code "153") (name "unconnected-(OLED3-D6-Pad22)") (class "Default")
      (node (ref "OLED3") (pin "22") (pinfunction "D6_22") (pintype "bidirectional"))
    )
    (net (code "154") (name "unconnected-(OLED3-D7-Pad23)") (class "Default")
      (node (ref "OLED3") (pin "23") (pinfunction "D7_23") (pintype "bidirectional"))
    )
    (net (code "155") (name "unconnected-(OLED3-E{slash}~{RD}-Pad15)") (class "Default")
      (node (ref "OLED3") (pin "15") (pinfunction "E/~{RD}_15") (pintype "bidirectional"))
    )
    (net (code "156") (name "unconnected-(OLED3-R{slash}~{W}-Pad14)") (class "Default")
      (node (ref "OLED3") (pin "14") (pinfunction "R/~{W}_14") (pintype "bidirectional"))
    )
    (net (code "157") (name "unconnected-(OLED4-D2-Pad18)") (class "Default")
      (node (ref "OLED4") (pin "18") (pinfunction "D2_18") (pintype "bidirectional"))
    )
    (net (code "158") (name "unconnected-(OLED4-D3-Pad19)") (class "Default")
      (node (ref "OLED4") (pin "19") (pinfunction "D3_19") (pintype "bidirectional"))
    )
    (net (code "159") (name "unconnected-(OLED4-D4-Pad20)") (class "Default")
      (node (ref "OLED4") (pin "20") (pinfunction "D4_20") (pintype "bidirectional"))
    )
    (net (code "160") (name "unconnected-(OLED4-D5-Pad21)") (class "Default")
      (node (ref "OLED4") (pin "21") (pinfunction "D5_21") (pintype "bidirectional"))
    )
    (net (code "161") (name "unconnected-(OLED4-D6-Pad22)") (class "Default")
      (node (ref "OLED4") (pin "22") (pinfunction "D6_22") (pintype "bidirectional"))
    )
    (net (code "162") (name "unconnected-(OLED4-D7-Pad23)") (class "Default")
      (node (ref "OLED4") (pin "23") (pinfunction "D7_23") (pintype "bidirectional"))
    )
    (net (code "163") (name "unconnected-(OLED4-E{slash}~{RD}-Pad15)") (class "Default")
      (node (ref "OLED4") (pin "15") (pinfunction "E/~{RD}_15") (pintype "bidirectional"))
    )
    (net (code "164") (name "unconnected-(OLED4-R{slash}~{W}-Pad14)") (class "Default")
      (node (ref "OLED4") (pin "14") (pinfunction "R/~{W}_14") (pintype "bidirectional"))
    )
    (net (code "165") (name "unconnected-(OLED5-D2-Pad18)") (class "Default")
      (node (ref "OLED5") (pin "18") (pinfunction "D2_18") (pintype "bidirectional"))
    )
    (net (code "166") (name "unconnected-(OLED5-D3-Pad19)") (class "Default")
      (node (ref "OLED5") (pin "19") (pinfunction "D3_19") (pintype "bidirectional"))
    )
    (net (code "167") (name "unconnected-(OLED5-D4-Pad20)") (class "Default")
      (node (ref "OLED5") (pin "20") (pinfunction "D4_20") (pintype "bidirectional"))
    )
    (net (code "168") (name "unconnected-(OLED5-D5-Pad21)") (class "Default")
      (node (ref "OLED5") (pin "21") (pinfunction "D5_21") (pintype "bidirectional"))
    )
    (net (code "169") (name "unconnected-(OLED5-D6-Pad22)") (class "Default")
      (node (ref "OLED5") (pin "22") (pinfunction "D6_22") (pintype "bidirectional"))
    )
    (net (code "170") (name "unconnected-(OLED5-D7-Pad23)") (class "Default")
      (node (ref "OLED5") (pin "23") (pinfunction "D7_23") (pintype "bidirectional"))
    )
    (net (code "171") (name "unconnected-(OLED5-E{slash}~{RD}-Pad15)") (class "Default")
      (node (ref "OLED5") (pin "15") (pinfunction "E/~{RD}_15") (pintype "bidirectional"))
    )
    (net (code "172") (name "unconnected-(OLED5-R{slash}~{W}-Pad14)") (class "Default")
      (node (ref "OLED5") (pin "14") (pinfunction "R/~{W}_14") (pintype "bidirectional"))
    )
    (net (code "173") (name "unconnected-(OLED6-D2-Pad18)") (class "Default")
      (node (ref "OLED6") (pin "18") (pinfunction "D2_18") (pintype "bidirectional"))
    )
    (net (code "174") (name "unconnected-(OLED6-D3-Pad19)") (class "Default")
      (node (ref "OLED6") (pin "19") (pinfunction "D3_19") (pintype "bidirectional"))
    )
    (net (code "175") (name "unconnected-(OLED6-D4-Pad20)") (class "Default")
      (node (ref "OLED6") (pin "20") (pinfunction "D4_20") (pintype "bidirectional"))
    )
    (net (code "176") (name "unconnected-(OLED6-D5-Pad21)") (class "Default")
      (node (ref "OLED6") (pin "21") (pinfunction "D5_21") (pintype "bidirectional"))
    )
    (net (code "177") (name "unconnected-(OLED6-D6-Pad22)") (class "Default")
      (node (ref "OLED6") (pin "22") (pinfunction "D6_22") (pintype "bidirectional"))
    )
    (net (code "178") (name "unconnected-(OLED6-D7-Pad23)") (class "Default")
      (node (ref "OLED6") (pin "23") (pinfunction "D7_23") (pintype "bidirectional"))
    )
    (net (code "179") (name "unconnected-(OLED6-E{slash}~{RD}-Pad15)") (class "Default")
      (node (ref "OLED6") (pin "15") (pinfunction "E/~{RD}_15") (pintype "bidirectional"))
    )
    (net (code "180") (name "unconnected-(OLED6-R{slash}~{W}-Pad14)") (class "Default")
      (node (ref "OLED6") (pin "14") (pinfunction "R/~{W}_14") (pintype "bidirectional"))
    )
    (net (code "181") (name "unconnected-(OLED7-D2-Pad18)") (class "Default")
      (node (ref "OLED7") (pin "18") (pinfunction "D2_18") (pintype "bidirectional"))
    )
    (net (code "182") (name "unconnected-(OLED7-D3-Pad19)") (class "Default")
      (node (ref "OLED7") (pin "19") (pinfunction "D3_19") (pintype "bidirectional"))
    )
    (net (code "183") (name "unconnected-(OLED7-D4-Pad20)") (class "Default")
      (node (ref "OLED7") (pin "20") (pinfunction "D4_20") (pintype "bidirectional"))
    )
    (net (code "184") (name "unconnected-(OLED7-D5-Pad21)") (class "Default")
      (node (ref "OLED7") (pin "21") (pinfunction "D5_21") (pintype "bidirectional"))
    )
    (net (code "185") (name "unconnected-(OLED7-D6-Pad22)") (class "Default")
      (node (ref "OLED7") (pin "22") (pinfunction "D6_22") (pintype "bidirectional"))
    )
    (net (code "186") (name "unconnected-(OLED7-D7-Pad23)") (class "Default")
      (node (ref "OLED7") (pin "23") (pinfunction "D7_23") (pintype "bidirectional"))
    )
    (net (code "187") (name "unconnected-(OLED7-E{slash}~{RD}-Pad15)") (class "Default")
      (node (ref "OLED7") (pin "15") (pinfunction "E/~{RD}_15") (pintype "bidirectional"))
    )
    (net (code "188") (name "unconnected-(OLED7-R{slash}~{W}-Pad14)") (class "Default")
      (node (ref "OLED7") (pin "14") (pinfunction "R/~{W}_14") (pintype "bidirectional"))
    )
    (net (code "189") (name "unconnected-(OLED8-D2-Pad18)") (class "Default")
      (node (ref "OLED8") (pin "18") (pinfunction "D2_18") (pintype "bidirectional"))
    )
    (net (code "190") (name "unconnected-(OLED8-D3-Pad19)") (class "Default")
      (node (ref "OLED8") (pin "19") (pinfunction "D3_19") (pintype "bidirectional"))
    )
    (net (code "191") (name "unconnected-(OLED8-D4-Pad20)") (class "Default")
      (node (ref "OLED8") (pin "20") (pinfunction "D4_20") (pintype "bidirectional"))
    )
    (net (code "192") (name "unconnected-(OLED8-D5-Pad21)") (class "Default")
      (node (ref "OLED8") (pin "21") (pinfunction "D5_21") (pintype "bidirectional"))
    )
    (net (code "193") (name "unconnected-(OLED8-D6-Pad22)") (class "Default")
      (node (ref "OLED8") (pin "22") (pinfunction "D6_22") (pintype "bidirectional"))
    )
    (net (code "194") (name "unconnected-(OLED8-D7-Pad23)") (class "Default")
      (node (ref "OLED8") (pin "23") (pinfunction "D7_23") (pintype "bidirectional"))
    )
    (net (code "195") (name "unconnected-(OLED8-E{slash}~{RD}-Pad15)") (class "Default")
      (node (ref "OLED8") (pin "15") (pinfunction "E/~{RD}_15") (pintype "bidirectional"))
    )
    (net (code "196") (name "unconnected-(OLED8-R{slash}~{W}-Pad14)") (class "Default")
      (node (ref "OLED8") (pin "14") (pinfunction "R/~{W}_14") (pintype "bidirectional"))
    )
    (net (code "197") (name "unconnected-(OLED9-D2-Pad18)") (class "Default")
      (node (ref "OLED9") (pin "18") (pinfunction "D2_18") (pintype "bidirectional"))
    )
    (net (code "198") (name "unconnected-(OLED9-D3-Pad19)") (class "Default")
      (node (ref "OLED9") (pin "19") (pinfunction "D3_19") (pintype "bidirectional"))
    )
    (net (code "199") (name "unconnected-(OLED9-D4-Pad20)") (class "Default")
      (node (ref "OLED9") (pin "20") (pinfunction "D4_20") (pintype "bidirectional"))
    )
    (net (code "200") (name "unconnected-(OLED9-D5-Pad21)") (class "Default")
      (node (ref "OLED9") (pin "21") (pinfunction "D5_21") (pintype "bidirectional"))
    )
    (net (code "201") (name "unconnected-(OLED9-D6-Pad22)") (class "Default")
      (node (ref "OLED9") (pin "22") (pinfunction "D6_22") (pintype "bidirectional"))
    )
    (net (code "202") (name "unconnected-(OLED9-D7-Pad23)") (class "Default")
      (node (ref "OLED9") (pin "23") (pinfunction "D7_23") (pintype "bidirectional"))
    )
    (net (code "203") (name "unconnected-(OLED9-E{slash}~{RD}-Pad15)") (class "Default")
      (node (ref "OLED9") (pin "15") (pinfunction "E/~{RD}_15") (pintype "bidirectional"))
    )
    (net (code "204") (name "unconnected-(OLED9-R{slash}~{W}-Pad14)") (class "Default")
      (node (ref "OLED9") (pin "14") (pinfunction "R/~{W}_14") (pintype "bidirectional"))
    )
    (net (code "205") (name "unconnected-(OLED10-D2-Pad18)") (class "Default")
      (node (ref "OLED10") (pin "18") (pinfunction "D2_18") (pintype "bidirectional"))
    )
    (net (code "206") (name "unconnected-(OLED10-D3-Pad19)") (class "Default")
      (node (ref "OLED10") (pin "19") (pinfunction "D3_19") (pintype "bidirectional"))
    )
    (net (code "207") (name "unconnected-(OLED10-D4-Pad20)") (class "Default")
      (node (ref "OLED10") (pin "20") (pinfunction "D4_20") (pintype "bidirectional"))
    )
    (net (code "208") (name "unconnected-(OLED10-D5-Pad21)") (class "Default")
      (node (ref "OLED10") (pin "21") (pinfunction "D5_21") (pintype "bidirectional"))
    )
    (net (code "209") (name "unconnected-(OLED10-D6-Pad22)") (class "Default")
      (node (ref "OLED10") (pin "22") (pinfunction "D6_22") (pintype "bidirectional"))
    )
    (net (code "210") (name "unconnected-(OLED10-D7-Pad23)") (class "Default")
      (node (ref "OLED10") (pin "23") (pinfunction "D7_23") (pintype "bidirectional"))
    )
    (net (code "211") (name "unconnected-(OLED10-E{slash}~{RD}-Pad15)") (class "Default")
      (node (ref "OLED10") (pin "15") (pinfunction "E/~{RD}_15") (pintype "bidirectional"))
    )
    (net (code "212") (name "unconnected-(OLED10-R{slash}~{W}-Pad14)") (class "Default")
      (node (ref "OLED10") (pin "14") (pinfunction "R/~{W}_14") (pintype "bidirectional"))
    )
    (net (code "213") (name "unconnected-(OLED11-D2-Pad18)") (class "Default")
      (node (ref "OLED11") (pin "18") (pinfunction "D2_18") (pintype "bidirectional"))
    )
    (net (code "214") (name "unconnected-(OLED11-D3-Pad19)") (class "Default")
      (node (ref "OLED11") (pin "19") (pinfunction "D3_19") (pintype "bidirectional"))
    )
    (net (code "215") (name "unconnected-(OLED11-D4-Pad20)") (class "Default")
      (node (ref "OLED11") (pin "20") (pinfunction "D4_20") (pintype "bidirectional"))
    )
    (net (code "216") (name "unconnected-(OLED11-D5-Pad21)") (class "Default")
      (node (ref "OLED11") (pin "21") (pinfunction "D5_21") (pintype "bidirectional"))
    )
    (net (code "217") (name "unconnected-(OLED11-D6-Pad22)") (class "Default")
      (node (ref "OLED11") (pin "22") (pinfunction "D6_22") (pintype "bidirectional"))
    )
    (net (code "218") (name "unconnected-(OLED11-D7-Pad23)") (class "Default")
      (node (ref "OLED11") (pin "23") (pinfunction "D7_23") (pintype "bidirectional"))
    )
    (net (code "219") (name "unconnected-(OLED11-E{slash}~{RD}-Pad15)") (class "Default")
      (node (ref "OLED11") (pin "15") (pinfunction "E/~{RD}_15") (pintype "bidirectional"))
    )
    (net (code "220") (name "unconnected-(OLED11-R{slash}~{W}-Pad14)") (class "Default")
      (node (ref "OLED11") (pin "14") (pinfunction "R/~{W}_14") (pintype "bidirectional"))
    )
    (net (code "221") (name "unconnected-(OLED12-D2-Pad18)") (class "Default")
      (node (ref "OLED12") (pin "18") (pinfunction "D2_18") (pintype "bidirectional"))
    )
    (net (code "222") (name "unconnected-(OLED12-D3-Pad19)") (class "Default")
      (node (ref "OLED12") (pin "19") (pinfunction "D3_19") (pintype "bidirectional"))
    )
    (net (code "223") (name "unconnected-(OLED12-D4-Pad20)") (class "Default")
      (node (ref "OLED12") (pin "20") (pinfunction "D4_20") (pintype "bidirectional"))
    )
    (net (code "224") (name "unconnected-(OLED12-D5-Pad21)") (class "Default")
      (node (ref "OLED12") (pin "21") (pinfunction "D5_21") (pintype "bidirectional"))
    )
    (net (code "225") (name "unconnected-(OLED12-D6-Pad22)") (class "Default")
      (node (ref "OLED12") (pin "22") (pinfunction "D6_22") (pintype "bidirectional"))
    )
    (net (code "226") (name "unconnected-(OLED12-D7-Pad23)") (class "Default")
      (node (ref "OLED12") (pin "23") (pinfunction "D7_23") (pintype "bidirectional"))
    )
    (net (code "227") (name "unconnected-(OLED12-E{slash}~{RD}-Pad15)") (class "Default")
      (node (ref "OLED12") (pin "15") (pinfunction "E/~{RD}_15") (pintype "bidirectional"))
    )
    (net (code "228") (name "unconnected-(OLED12-R{slash}~{W}-Pad14)") (class "Default")
      (node (ref "OLED12") (pin "14") (pinfunction "R/~{W}_14") (pintype "bidirectional"))
    )
    (net (code "229") (name "unconnected-(SW2-P1-PadA')") (class "Default")
      (node (ref "SW2") (pin "A'") (pinfunction "P1_A'") (pintype "passive"))
    )
    (net (code "230") (name "unconnected-(U3-BP-Pad4)") (class "Default")
      (node (ref "U3") (pin "4") (pinfunction "BP_4") (pintype "input"))
    )
    (net (code "231") (name "unconnected-(UC1-PA0_WKUP{slash}USART2_CTS{slash}ADC12_IN0{slash}TIM2_CH1_ETR-Pad10)") (class "Default")
      (node (ref "UC1") (pin "10") (pinfunction "PA0_WKUP/USART2_CTS/ADC12_IN0/TIM2_CH1_ETR_10") (pintype "bidirectional"))
    )
    (net (code "232") (name "unconnected-(UC1-PA13{slash}JTMS{slash}SWDIO-Pad34)") (class "Default")
      (node (ref "UC1") (pin "34") (pinfunction "PA13/JTMS/SWDIO_34") (pintype "bidirectional"))
    )
    (net (code "233") (name "unconnected-(UC1-PC13-TAMPER-RTC-Pad2)") (class "Default")
      (node (ref "UC1") (pin "2") (pinfunction "PC13-TAMPER-RTC_2") (pintype "input"))
    )
  )
)
